# Roland_memser2308.net
KiCad netlist of a schematic drawn in EAGLE
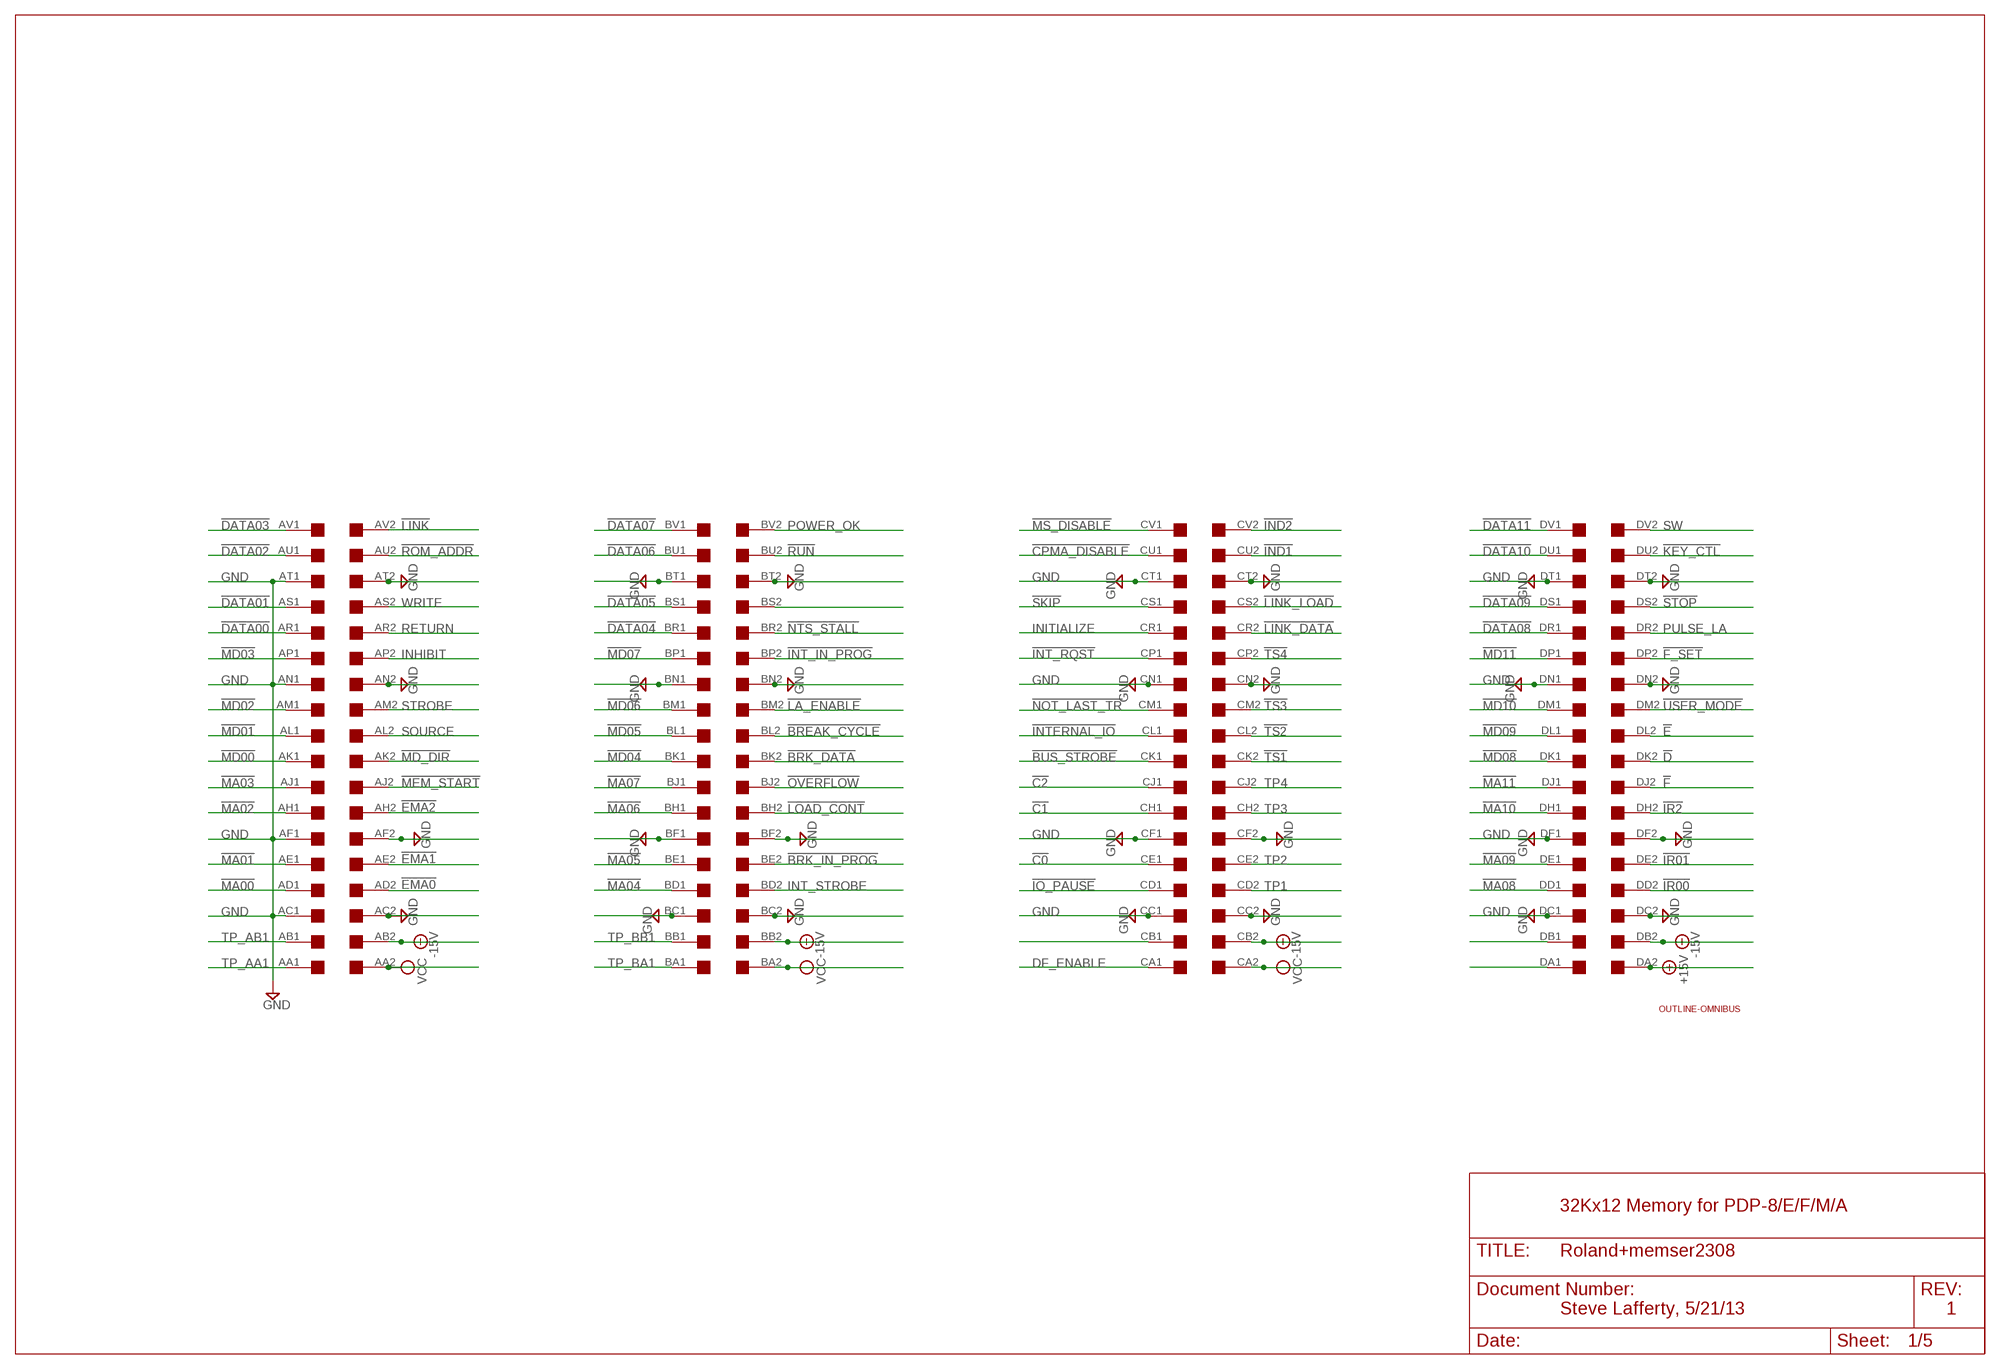
[diagram p0: schematic, sheet 1]
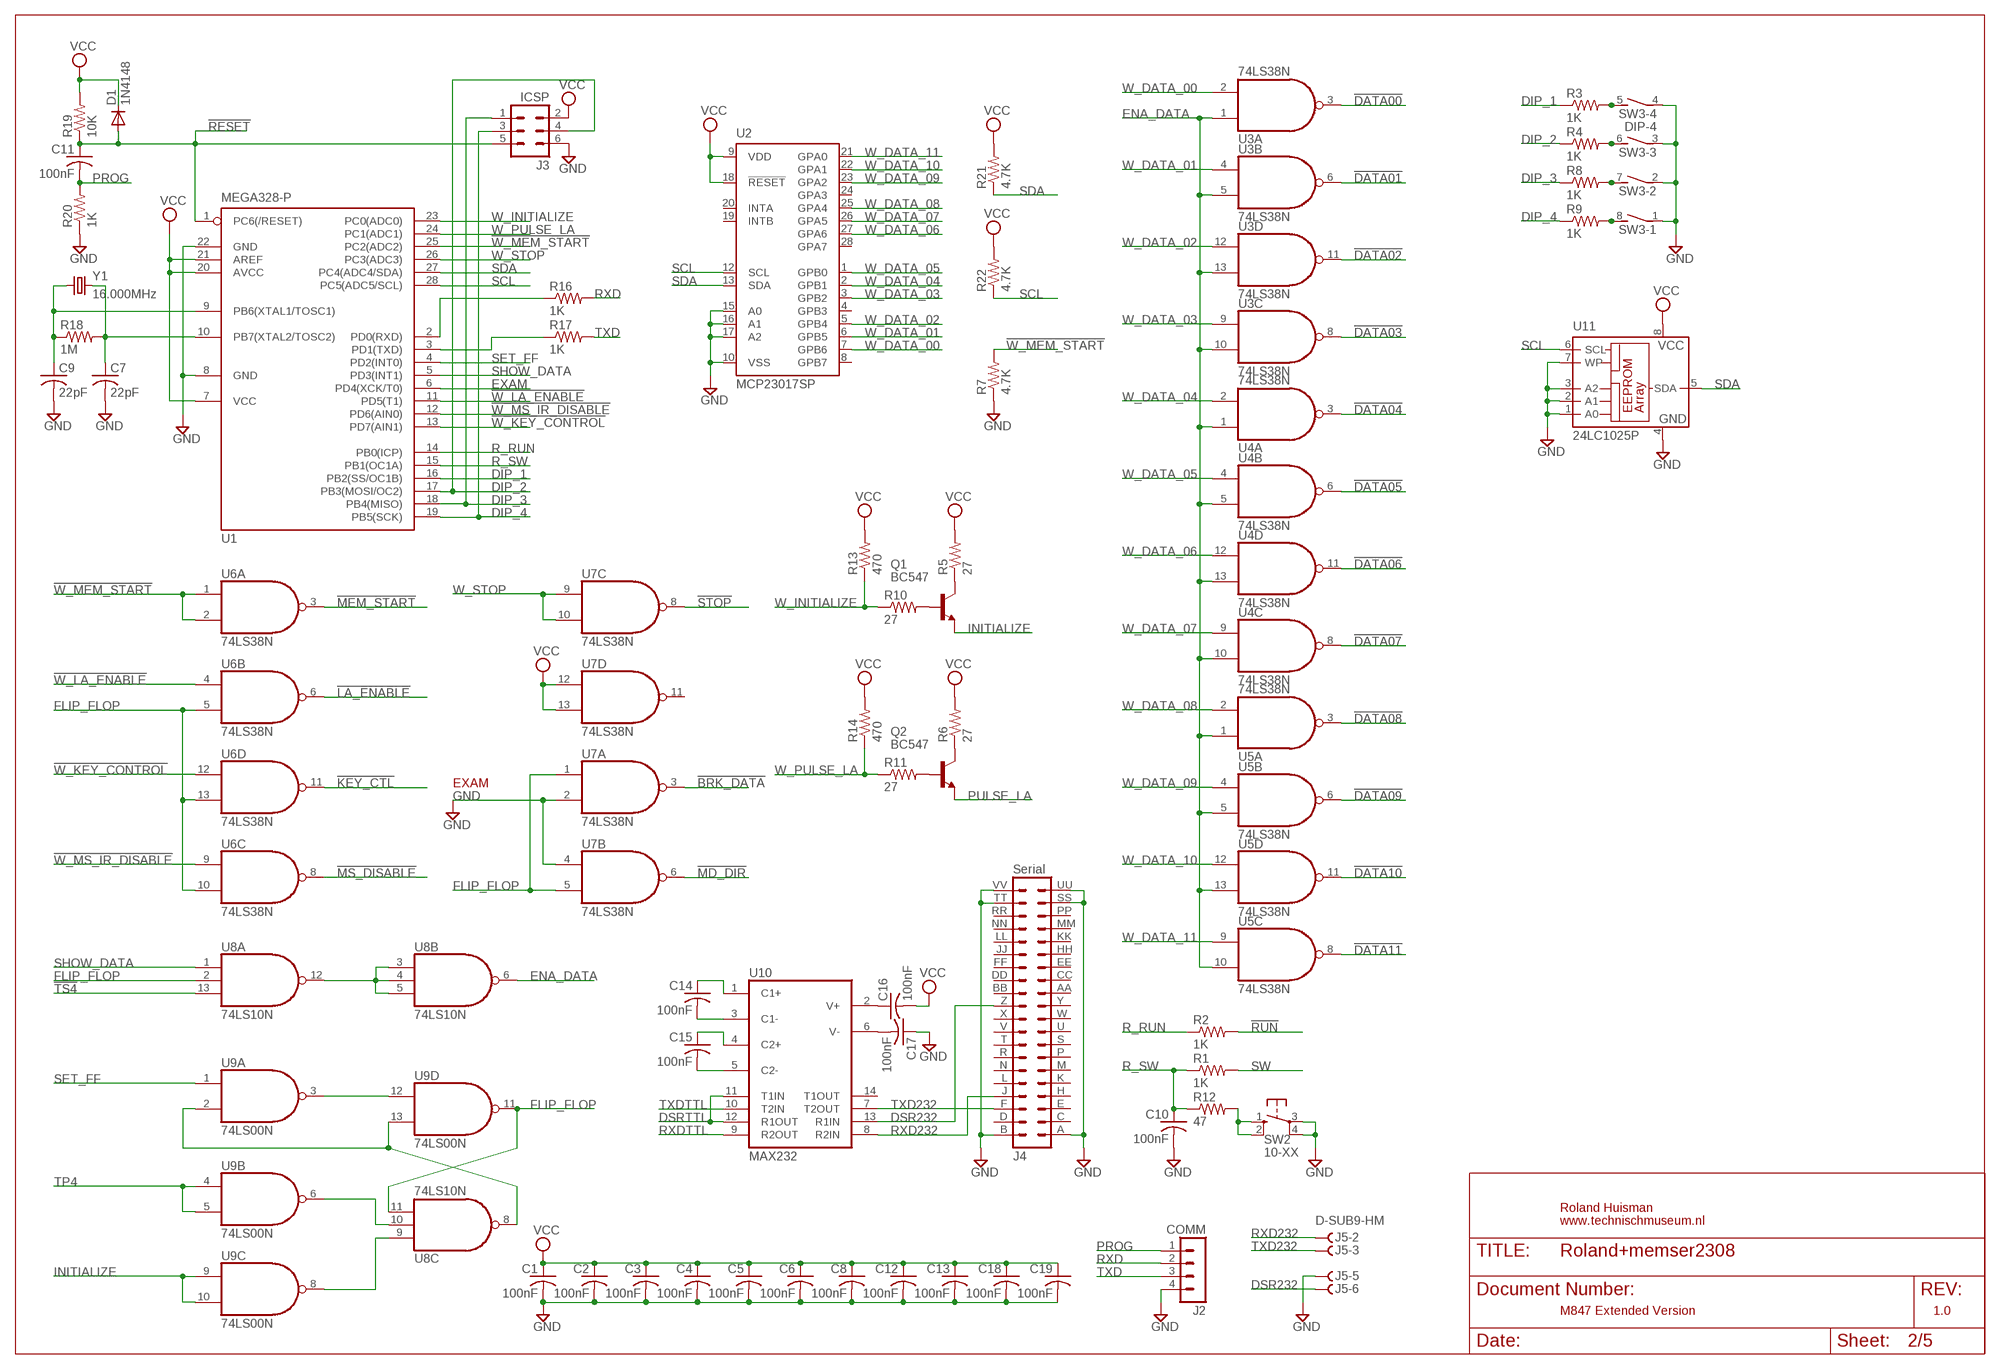
[diagram p1: schematic, sheet 2]
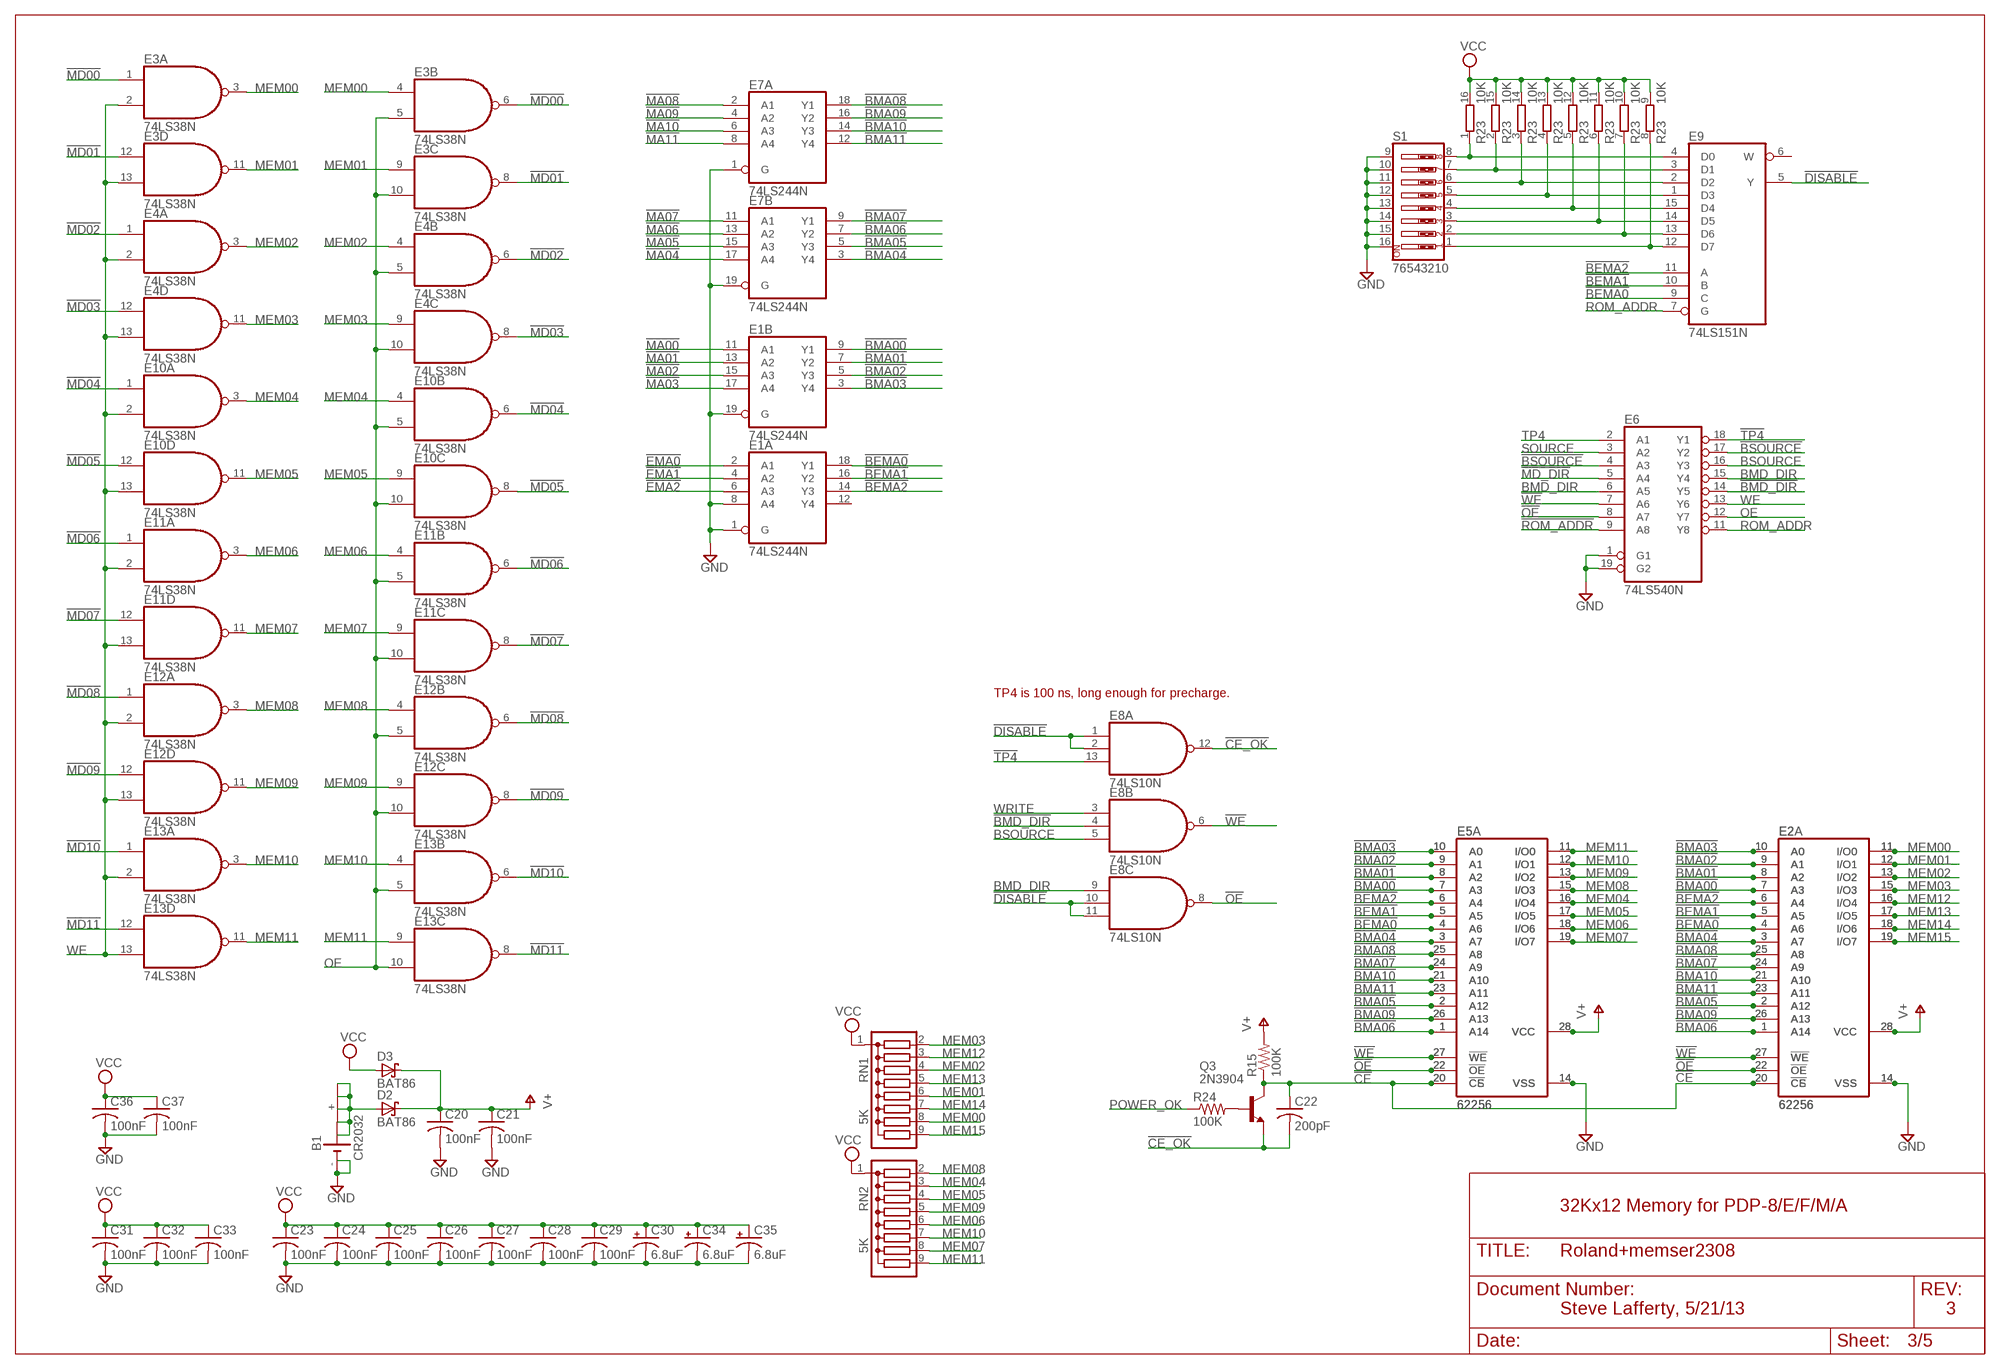
[diagram p2: schematic, sheet 3]
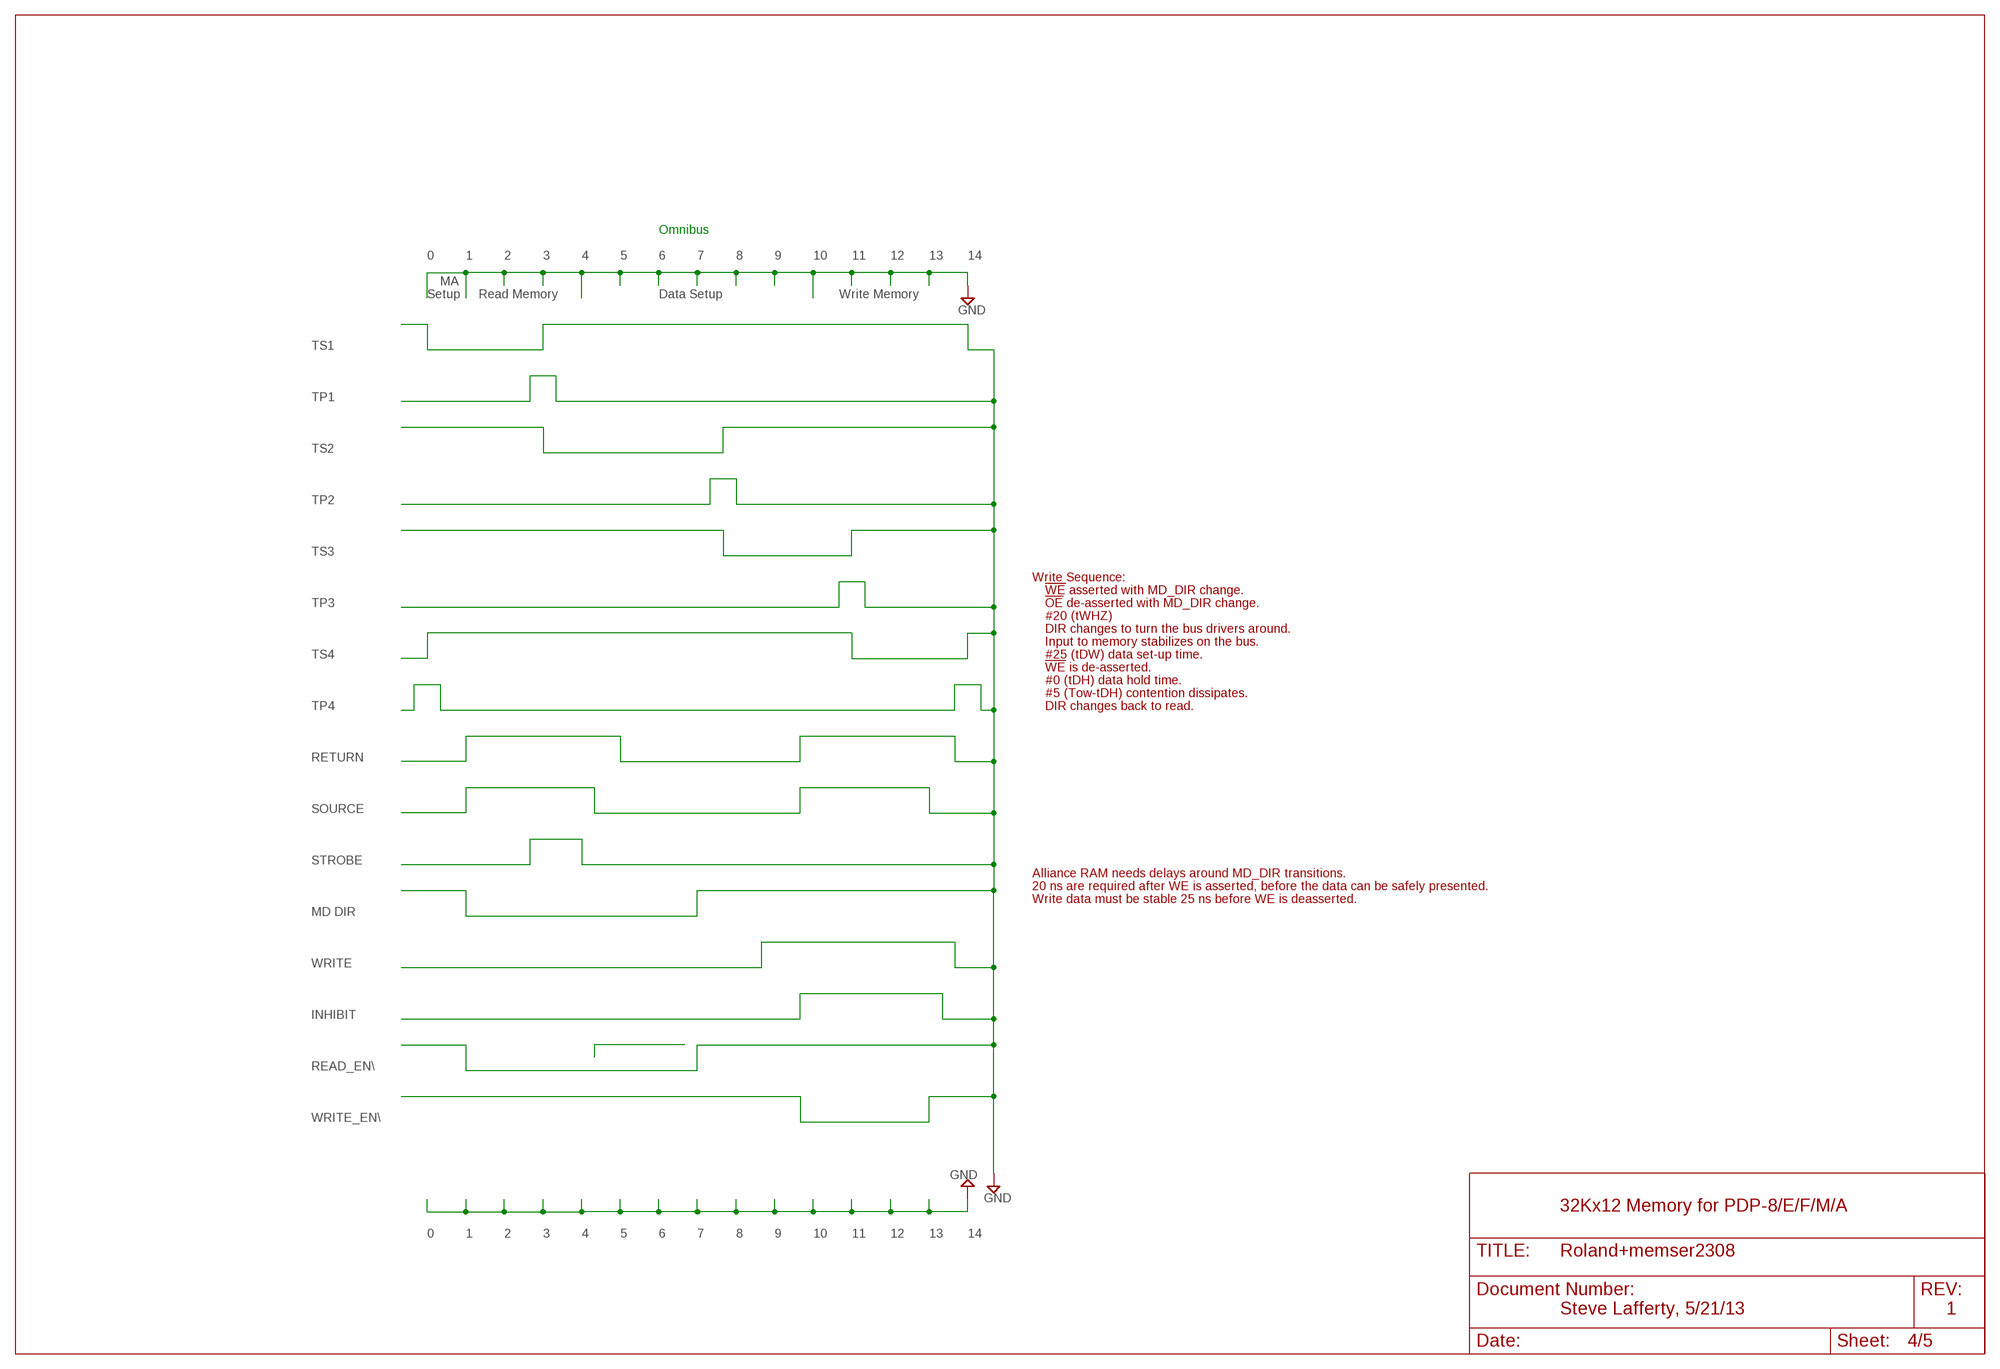
[diagram p3: schematic, sheet 4]
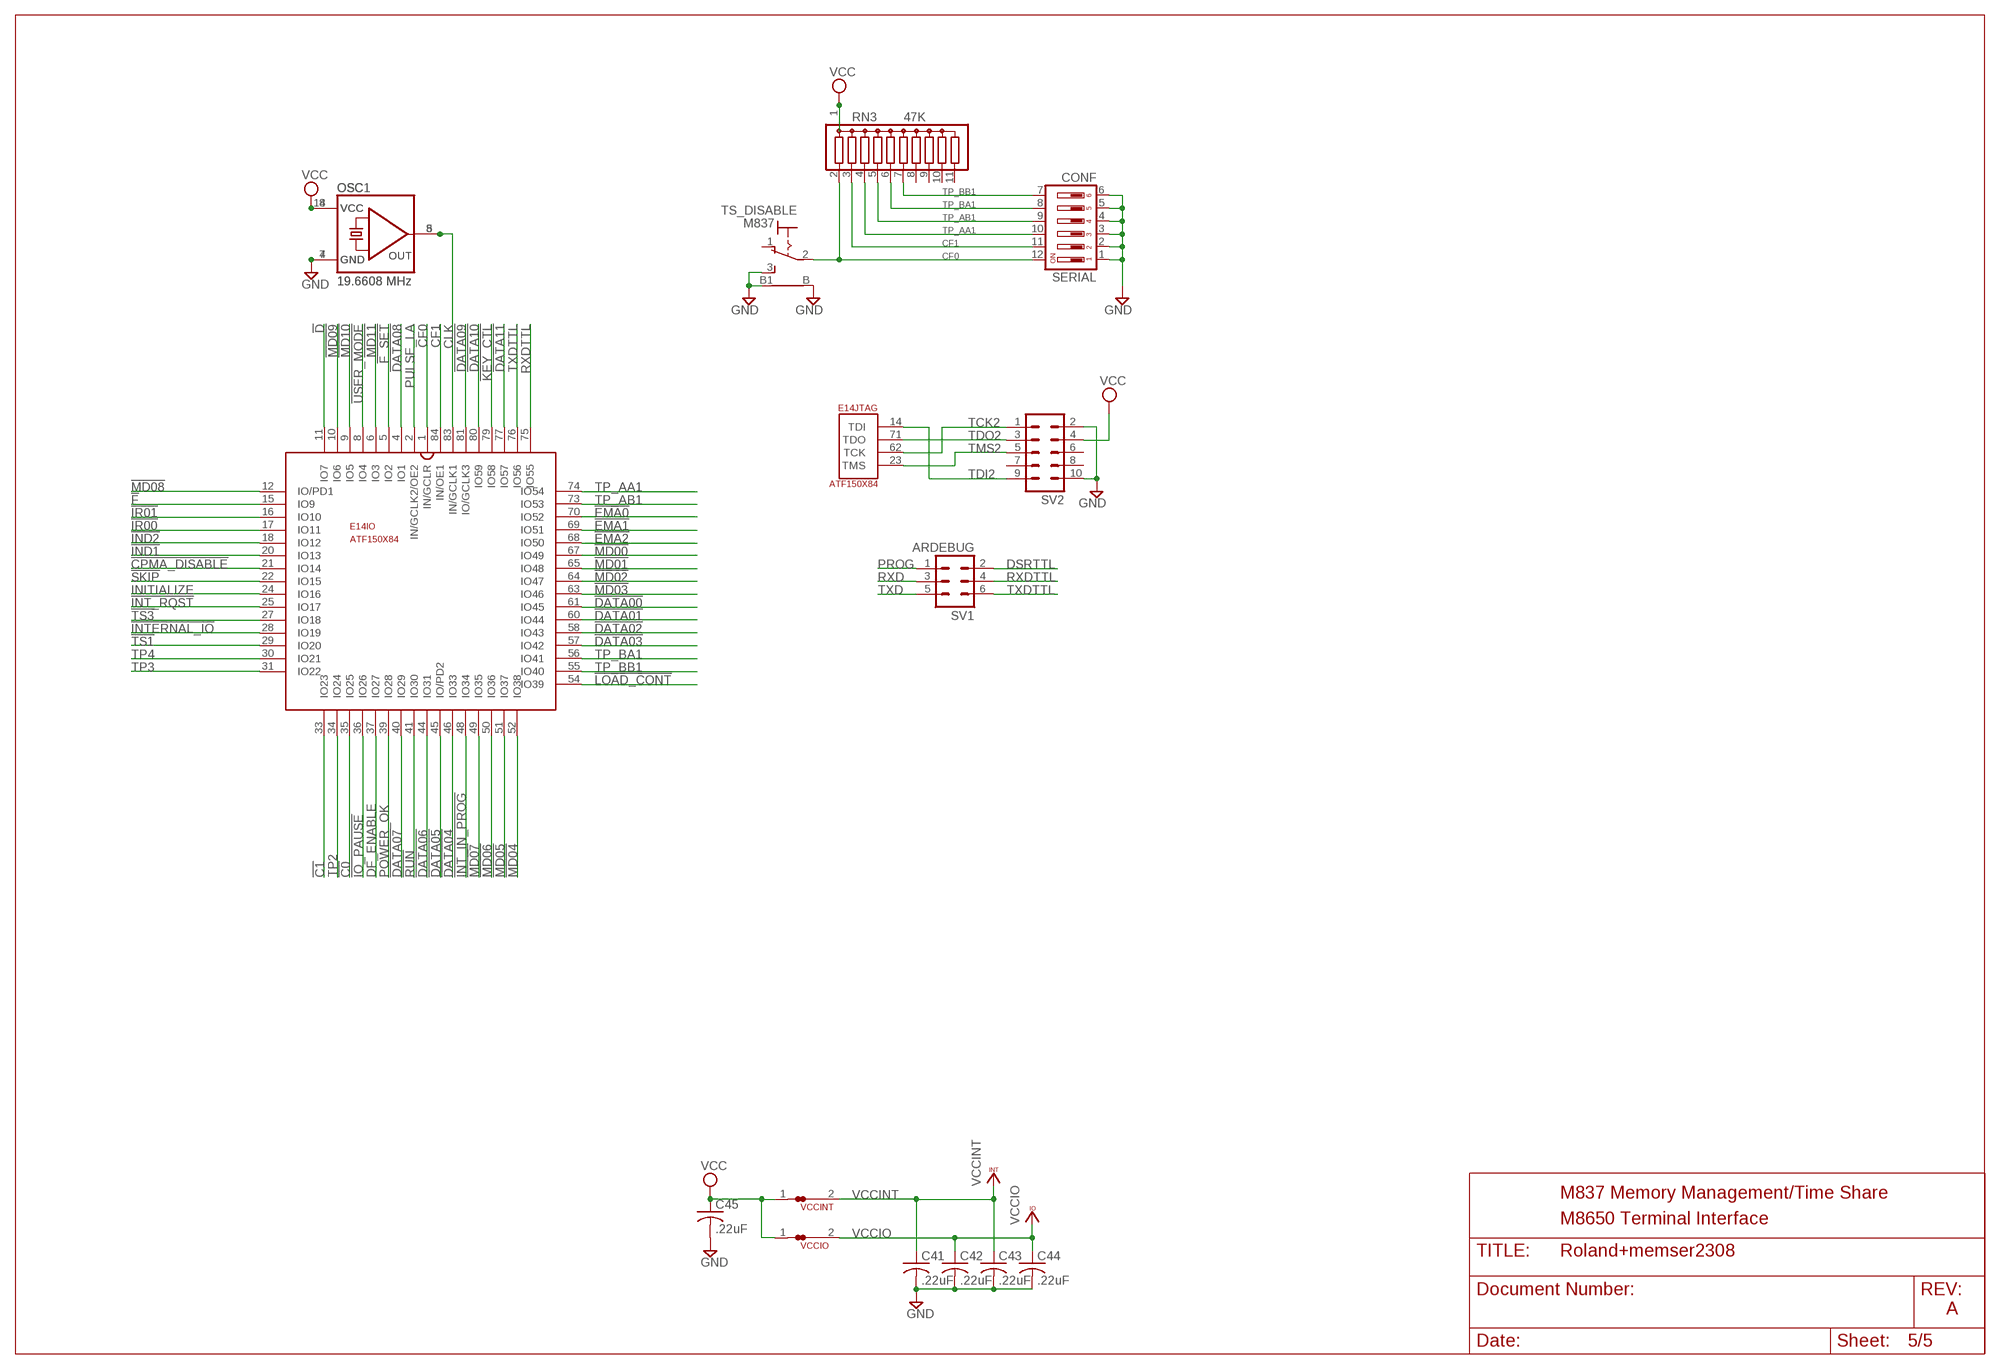
[diagram p4: schematic, sheet 5]

(export (version "E")
  (design (tool "Eeschema 10.0.6"))
  (components
    (comp (ref "C41")
      (value ".22uF")
      (footprint "eagle-import:C063-025X075")
      (libsource (lib "eagle-import") (part "C-US"))
    )
    (comp (ref "C42")
      (value ".22uF")
      (footprint "eagle-import:C063-025X075")
      (libsource (lib "eagle-import") (part "C-US"))
    )
    (comp (ref "C43")
      (value ".22uF")
      (footprint "eagle-import:C063-025X075")
      (libsource (lib "eagle-import") (part "C-US"))
    )
    (comp (ref "C44")
      (value ".22uF")
      (footprint "eagle-import:C063-025X075")
      (libsource (lib "eagle-import") (part "C-US"))
    )
    (comp (ref "C45")
      (value ".22uF")
      (footprint "eagle-import:C063-025X075")
      (libsource (lib "eagle-import") (part "C-US"))
    )
    (comp (ref "E14")
      (value "ATF150X84")
      (footprint "eagle-import:S84")
      (libsource (lib "eagle-import") (part "ATF150X84"))
    )
    (comp (ref "OSC")
      (value "19.6608 MHz")
      (footprint "eagle-import:DIL08S")
      (libsource (lib "eagle-import") (part "QG5460"))
    )
    (comp (ref "OSC1")
      (value "19.6608 MHz")
      (footprint "eagle-import:DIL14S")
      (libsource (lib "eagle-import") (part "QG5860"))
    )
    (comp (ref "RN3")
      (value "47K")
      (footprint "eagle-import:SIL11")
      (libsource (lib "eagle-import") (part "G10R"))
    )
    (comp (ref "SERIAL")
      (value "CONF")
      (footprint "eagle-import:DP-06")
      (fields (field (name "MPN") "MCDP06"))
      (libsource (lib "eagle-import") (part "DP06"))
    )
    (comp (ref "SV1")
      (value "ARDEBUG")
      (footprint "eagle-import:MA03-2")
      (libsource (lib "eagle-import") (part "MA03-2"))
    )
    (comp (ref "SV2")
      (value "ML10")
      (footprint "eagle-import:ML10")
      (libsource (lib "eagle-import") (part "ML10"))
    )
    (comp (ref "TS_DISABLE")
      (value "M837")
      (footprint "eagle-import:9070-1W")
      (libsource (lib "eagle-import") (part "9070-1W"))
    )
    (comp (ref "VCCINT")
      (value "JUMPER-NC1")
      (footprint "eagle-import:NC1")
      (libsource (lib "eagle-import") (part "JUMPER-NC1"))
    )
    (comp (ref "VCCIO")
      (value "JUMPER-NC1")
      (footprint "eagle-import:NC1")
      (libsource (lib "eagle-import") (part "JUMPER-NC1"))
    )
    (comp (ref "J1")
      (value "EDGE")
      (footprint "eagle-import:EDGE-CON8")
      (libsource (lib "eagle-import") (part "QUAD"))
    )
    (comp (ref "U$1")
      (value "OUTLINE-OMNIBUS")
      (footprint "eagle-import:OMNIBUS")
      (libsource (lib "eagle-import") (part "OUTLINE-OMNIBUS"))
    )
    (comp (ref "C1")
      (value "100nF")
      (footprint "eagle-import:C050-025X075")
      (libsource (lib "eagle-import") (part "C-US050-025X075"))
    )
    (comp (ref "C2")
      (value "100nF")
      (footprint "eagle-import:C050-025X075")
      (libsource (lib "eagle-import") (part "C-US050-025X075"))
    )
    (comp (ref "C3")
      (value "100nF")
      (footprint "eagle-import:C050-025X075")
      (libsource (lib "eagle-import") (part "C-US050-025X075"))
    )
    (comp (ref "C4")
      (value "100nF")
      (footprint "eagle-import:C050-025X075")
      (libsource (lib "eagle-import") (part "C-US050-025X075"))
    )
    (comp (ref "C5")
      (value "100nF")
      (footprint "eagle-import:C050-025X075")
      (libsource (lib "eagle-import") (part "C-US050-025X075"))
    )
    (comp (ref "C6")
      (value "100nF")
      (footprint "eagle-import:C050-025X075")
      (libsource (lib "eagle-import") (part "C-US050-025X075"))
    )
    (comp (ref "C7")
      (value "22pF")
      (footprint "eagle-import:C050-025X075")
      (libsource (lib "eagle-import") (part "C-US050-025X075"))
    )
    (comp (ref "C8")
      (value "100nF")
      (footprint "eagle-import:C050-025X075")
      (libsource (lib "eagle-import") (part "C-US050-025X075"))
    )
    (comp (ref "C9")
      (value "22pF")
      (footprint "eagle-import:C050-025X075")
      (libsource (lib "eagle-import") (part "C-US050-025X075"))
    )
    (comp (ref "C10")
      (value "100nF")
      (footprint "eagle-import:C050-025X075")
      (libsource (lib "eagle-import") (part "C-US050-025X075"))
    )
    (comp (ref "C11")
      (value "100nF")
      (footprint "eagle-import:C050-025X075")
      (libsource (lib "eagle-import") (part "C-US050-025X075"))
    )
    (comp (ref "C12")
      (value "100nF")
      (footprint "eagle-import:C050-025X075")
      (libsource (lib "eagle-import") (part "C-US050-025X075"))
    )
    (comp (ref "C13")
      (value "100nF")
      (footprint "eagle-import:C050-025X075")
      (libsource (lib "eagle-import") (part "C-US050-025X075"))
    )
    (comp (ref "C14")
      (value "100nF")
      (footprint "eagle-import:C050-025X075")
      (libsource (lib "eagle-import") (part "C-US050-025X075"))
    )
    (comp (ref "C15")
      (value "100nF")
      (footprint "eagle-import:C050-025X075")
      (libsource (lib "eagle-import") (part "C-US050-025X075"))
    )
    (comp (ref "C16")
      (value "100nF")
      (footprint "eagle-import:C050-025X075")
      (libsource (lib "eagle-import") (part "C-US050-025X075"))
    )
    (comp (ref "C17")
      (value "100nF")
      (footprint "eagle-import:C050-025X075")
      (libsource (lib "eagle-import") (part "C-US050-025X075"))
    )
    (comp (ref "C18")
      (value "100nF")
      (footprint "eagle-import:C050-025X075")
      (libsource (lib "eagle-import") (part "C-US050-025X075"))
    )
    (comp (ref "C19")
      (value "100nF")
      (footprint "eagle-import:C050-025X075")
      (libsource (lib "eagle-import") (part "C-US050-025X075"))
    )
    (comp (ref "D1")
      (value "1N4148")
      (footprint "eagle-import:DO35-10")
      (libsource (lib "eagle-import") (part "1N4148DO35-10"))
    )
    (comp (ref "J2")
      (value "COMM")
      (footprint "eagle-import:MA04-1")
      (libsource (lib "eagle-import") (part "MA04-1"))
    )
    (comp (ref "J3")
      (value "ICSP")
      (footprint "eagle-import:MA03-2")
      (libsource (lib "eagle-import") (part "MA03-2"))
    )
    (comp (ref "J4")
      (value "Serial")
      (footprint "eagle-import:DEC40PINH")
      (libsource (lib "eagle-import") (part "DEC40PINH"))
    )
    (comp (ref "J5")
      (value "D-SUB9-HM")
      (footprint "eagle-import:H5M09RA")
      (libsource (lib "eagle-import") (part "D-SUB9-H5M09RA"))
    )
    (comp (ref "Q1")
      (value "BC547")
      (footprint "eagle-import:TO5")
      (libsource (lib "eagle-import") (part "-NPN-TO5"))
    )
    (comp (ref "Q2")
      (value "BC547")
      (footprint "eagle-import:TO5")
      (libsource (lib "eagle-import") (part "-NPN-TO5"))
    )
    (comp (ref "R1")
      (value "1K")
      (footprint "eagle-import:0207_10")
      (libsource (lib "eagle-import") (part "R-US_0207/10"))
    )
    (comp (ref "R2")
      (value "1K")
      (footprint "eagle-import:0207_10")
      (libsource (lib "eagle-import") (part "R-US_0207/10"))
    )
    (comp (ref "R3")
      (value "1K")
      (footprint "eagle-import:0207_10")
      (libsource (lib "eagle-import") (part "R-US_0207/10"))
    )
    (comp (ref "R4")
      (value "1K")
      (footprint "eagle-import:0207_10")
      (libsource (lib "eagle-import") (part "R-US_0207/10"))
    )
    (comp (ref "R5")
      (value "27")
      (footprint "eagle-import:0207_10")
      (libsource (lib "eagle-import") (part "R-US_0207/10"))
    )
    (comp (ref "R6")
      (value "27")
      (footprint "eagle-import:0207_10")
      (libsource (lib "eagle-import") (part "R-US_0207/10"))
    )
    (comp (ref "R7")
      (value "4.7K")
      (footprint "eagle-import:0207_10")
      (libsource (lib "eagle-import") (part "R-US_0207/10"))
    )
    (comp (ref "R8")
      (value "1K")
      (footprint "eagle-import:0207_10")
      (libsource (lib "eagle-import") (part "R-US_0207/10"))
    )
    (comp (ref "R9")
      (value "1K")
      (footprint "eagle-import:0207_10")
      (libsource (lib "eagle-import") (part "R-US_0207/10"))
    )
    (comp (ref "R10")
      (value "27")
      (footprint "eagle-import:0207_10")
      (libsource (lib "eagle-import") (part "R-US_0207/10"))
    )
    (comp (ref "R11")
      (value "27")
      (footprint "eagle-import:0207_10")
      (libsource (lib "eagle-import") (part "R-US_0207/10"))
    )
    (comp (ref "R12")
      (value "47")
      (footprint "eagle-import:0207_10")
      (libsource (lib "eagle-import") (part "R-US_0207/10"))
    )
    (comp (ref "R13")
      (value "470")
      (footprint "eagle-import:0207_10")
      (libsource (lib "eagle-import") (part "R-US_0207/10"))
    )
    (comp (ref "R14")
      (value "470")
      (footprint "eagle-import:0207_10")
      (libsource (lib "eagle-import") (part "R-US_0207/10"))
    )
    (comp (ref "R16")
      (value "1K")
      (footprint "eagle-import:0207_10")
      (libsource (lib "eagle-import") (part "R-US_0207/10"))
    )
    (comp (ref "R17")
      (value "1K")
      (footprint "eagle-import:0207_10")
      (libsource (lib "eagle-import") (part "R-US_0207/10"))
    )
    (comp (ref "R18")
      (value "1M")
      (footprint "eagle-import:0207_10")
      (libsource (lib "eagle-import") (part "R-US_0207/10"))
    )
    (comp (ref "R19")
      (value "10K")
      (footprint "eagle-import:0207_10")
      (libsource (lib "eagle-import") (part "R-US_0207/10"))
    )
    (comp (ref "R20")
      (value "1K")
      (footprint "eagle-import:0207_10")
      (libsource (lib "eagle-import") (part "R-US_0207/10"))
    )
    (comp (ref "R21")
      (value "4.7K")
      (footprint "eagle-import:0207_10")
      (libsource (lib "eagle-import") (part "R-US_0207/10"))
    )
    (comp (ref "R22")
      (value "4.7K")
      (footprint "eagle-import:0207_10")
      (libsource (lib "eagle-import") (part "R-US_0207/10"))
    )
    (comp (ref "SW2")
      (value "10-XX")
      (footprint "eagle-import:B3F-10XX")
      (fields (field (name "MPN") "B3F-1000"))
      (libsource (lib "eagle-import") (part "10-XX"))
    )
    (comp (ref "SW3")
      (value "DIP-4")
      (footprint "eagle-import:DIP04S")
      (libsource (lib "eagle-import") (part "DIP04S"))
    )
    (comp (ref "U1")
      (value "MEGA328-P")
      (footprint "eagle-import:DIL28-3")
      (libsource (lib "eagle-import") (part "MEGA8-P"))
    )
    (comp (ref "U2")
      (value "MCP23017SP")
      (footprint "eagle-import:DIL28-3")
      (fields (field (name "MF") "MICROCHIP") (field (name "MPN") "MCP23017-E/SP"))
      (libsource (lib "eagle-import") (part "MCP23017SP"))
    )
    (comp (ref "U3")
      (value "74LS38N")
      (footprint "eagle-import:DIL14")
      (libsource (lib "eagle-import") (part "7438NLS"))
    )
    (comp (ref "U4")
      (value "74LS38N")
      (footprint "eagle-import:DIL14")
      (libsource (lib "eagle-import") (part "7438NLS"))
    )
    (comp (ref "U5")
      (value "74LS38N")
      (footprint "eagle-import:DIL14")
      (libsource (lib "eagle-import") (part "7438NLS"))
    )
    (comp (ref "U6")
      (value "74LS38N")
      (footprint "eagle-import:DIL14")
      (libsource (lib "eagle-import") (part "7438NLS"))
    )
    (comp (ref "U7")
      (value "74LS38N")
      (footprint "eagle-import:DIL14")
      (libsource (lib "eagle-import") (part "7438NLS"))
    )
    (comp (ref "U8")
      (value "74LS10N")
      (footprint "eagle-import:DIL14")
      (libsource (lib "eagle-import") (part "7410NLS"))
    )
    (comp (ref "U9")
      (value "74LS00N")
      (footprint "eagle-import:DIL14")
      (libsource (lib "eagle-import") (part "7400NLS"))
    )
    (comp (ref "U10")
      (value "MAX232")
      (footprint "eagle-import:DIL16")
      (fields (field (name "MF") "MAXIM") (field (name "MPN") "MAX232ACPE+"))
      (libsource (lib "eagle-import") (part "MAX232"))
    )
    (comp (ref "U11")
      (value "24LC1025P")
      (footprint "eagle-import:DIL8")
      (fields (field (name "MF") "MICROCHIP") (field (name "MPN") "24LC025-I/P"))
      (libsource (lib "eagle-import") (part "24PLC025"))
    )
    (comp (ref "Y1")
      (value "16.000MHz")
      (footprint "eagle-import:HC49U-H")
      (libsource (lib "eagle-import") (part "CRYSTALHC49U-H"))
    )
    (comp (ref "B1")
      (value "CR2032")
      (footprint "eagle-import:B2430UNI")
      (libsource (lib "eagle-import") (part "B2430UNI"))
    )
    (comp (ref "C20")
      (value "100nF")
      (footprint "eagle-import:C050-025X075")
      (libsource (lib "eagle-import") (part "C-US050-025X075"))
    )
    (comp (ref "C21")
      (value "100nF")
      (footprint "eagle-import:C050-025X075")
      (libsource (lib "eagle-import") (part "C-US050-025X075"))
    )
    (comp (ref "C22")
      (value "200pF")
      (footprint "eagle-import:C050-025X075")
      (libsource (lib "eagle-import") (part "C-US050-025X075"))
    )
    (comp (ref "C23")
      (value "100nF")
      (footprint "eagle-import:C050-025X075")
      (libsource (lib "eagle-import") (part "C-US050-025X075"))
    )
    (comp (ref "C24")
      (value "100nF")
      (footprint "eagle-import:C050-025X075")
      (libsource (lib "eagle-import") (part "C-US050-025X075"))
    )
    (comp (ref "C25")
      (value "100nF")
      (footprint "eagle-import:C050-025X075")
      (libsource (lib "eagle-import") (part "C-US050-025X075"))
    )
    (comp (ref "C26")
      (value "100nF")
      (footprint "eagle-import:C050-025X075")
      (libsource (lib "eagle-import") (part "C-US050-025X075"))
    )
    (comp (ref "C27")
      (value "100nF")
      (footprint "eagle-import:C050-025X075")
      (libsource (lib "eagle-import") (part "C-US050-025X075"))
    )
    (comp (ref "C28")
      (value "100nF")
      (footprint "eagle-import:C050-025X075")
      (libsource (lib "eagle-import") (part "C-US050-025X075"))
    )
    (comp (ref "C29")
      (value "100nF")
      (footprint "eagle-import:C050-025X075")
      (libsource (lib "eagle-import") (part "C-US050-025X075"))
    )
    (comp (ref "C30")
      (value "6.8uF")
      (footprint "eagle-import:E12-8")
      (libsource (lib "eagle-import") (part "CPOL-USE20-8AXIAL"))
    )
    (comp (ref "C31")
      (value "100nF")
      (footprint "eagle-import:C050-025X075")
      (libsource (lib "eagle-import") (part "C-US050-025X075"))
    )
    (comp (ref "C32")
      (value "100nF")
      (footprint "eagle-import:C050-025X075")
      (libsource (lib "eagle-import") (part "C-US050-025X075"))
    )
    (comp (ref "C33")
      (value "100nF")
      (footprint "eagle-import:C050-025X075")
      (libsource (lib "eagle-import") (part "C-US050-025X075"))
    )
    (comp (ref "C34")
      (value "6.8uF")
      (footprint "eagle-import:E12-8")
      (libsource (lib "eagle-import") (part "CPOL-USE20-8AXIAL"))
    )
    (comp (ref "C35")
      (value "6.8uF")
      (footprint "eagle-import:E12-8")
      (libsource (lib "eagle-import") (part "CPOL-USE20-8AXIAL"))
    )
    (comp (ref "C36")
      (value "100nF")
      (footprint "eagle-import:C050-025X075")
      (libsource (lib "eagle-import") (part "C-US050-025X075"))
    )
    (comp (ref "C37")
      (value "100nF")
      (footprint "eagle-import:C050-025X075")
      (libsource (lib "eagle-import") (part "C-US050-025X075"))
    )
    (comp (ref "D2")
      (value "BAT86")
      (footprint "eagle-import:DO35-10")
      (libsource (lib "eagle-import") (part "BAT19"))
    )
    (comp (ref "D3")
      (value "BAT86")
      (footprint "eagle-import:DO35-10")
      (libsource (lib "eagle-import") (part "BAT19"))
    )
    (comp (ref "E1")
      (value "74LS244N")
      (footprint "eagle-import:DIL20")
      (libsource (lib "eagle-import") (part "74244NLS"))
    )
    (comp (ref "E2")
      (value "62256")
      (footprint "eagle-import:DIL28-6")
      (libsource (lib "eagle-import") (part "58C256P"))
    )
    (comp (ref "E2A")
      (value "62256")
      (footprint "eagle-import:DIL28-3")
      (libsource (lib "eagle-import") (part "62832P"))
    )
    (comp (ref "E3")
      (value "74LS38N")
      (footprint "eagle-import:DIL14")
      (libsource (lib "eagle-import") (part "7438NLS"))
    )
    (comp (ref "E4")
      (value "74LS38N")
      (footprint "eagle-import:DIL14")
      (libsource (lib "eagle-import") (part "7438NLS"))
    )
    (comp (ref "E5")
      (value "62256")
      (footprint "eagle-import:DIL28-6")
      (libsource (lib "eagle-import") (part "58C256P"))
    )
    (comp (ref "E5A")
      (value "62256")
      (footprint "eagle-import:DIL28-3")
      (libsource (lib "eagle-import") (part "62832P"))
    )
    (comp (ref "E6")
      (value "74LS540N")
      (footprint "eagle-import:DIL20")
      (libsource (lib "eagle-import") (part "74540NLS"))
    )
    (comp (ref "E7")
      (value "74LS244N")
      (footprint "eagle-import:DIL20")
      (libsource (lib "eagle-import") (part "74244NLS"))
    )
    (comp (ref "E8")
      (value "74LS10N")
      (footprint "eagle-import:DIL14")
      (libsource (lib "eagle-import") (part "7410NLS"))
    )
    (comp (ref "E9")
      (value "74LS151N")
      (footprint "eagle-import:DIL16")
      (libsource (lib "eagle-import") (part "74151NLS"))
    )
    (comp (ref "E10")
      (value "74LS38N")
      (footprint "eagle-import:DIL14")
      (libsource (lib "eagle-import") (part "7438NLS"))
    )
    (comp (ref "E11")
      (value "74LS38N")
      (footprint "eagle-import:DIL14")
      (libsource (lib "eagle-import") (part "7438NLS"))
    )
    (comp (ref "E12")
      (value "74LS38N")
      (footprint "eagle-import:DIL14")
      (libsource (lib "eagle-import") (part "7438NLS"))
    )
    (comp (ref "E13")
      (value "74LS38N")
      (footprint "eagle-import:DIL14")
      (libsource (lib "eagle-import") (part "7438NLS"))
    )
    (comp (ref "Q3")
      (value "2N3904")
      (footprint "eagle-import:TO92")
      (libsource (lib "eagle-import") (part "2N3904"))
    )
    (comp (ref "R15")
      (value "100K")
      (footprint "eagle-import:0207_10")
      (libsource (lib "eagle-import") (part "R-US_0207/10"))
    )
    (comp (ref "R23")
      (value "10K")
      (footprint "eagle-import:DIL16")
      (libsource (lib "eagle-import") (part "8R-P"))
    )
    (comp (ref "R24")
      (value "100K")
      (footprint "eagle-import:0207_10")
      (libsource (lib "eagle-import") (part "R-US_0207/10"))
    )
    (comp (ref "RN1")
      (value "5K")
      (footprint "eagle-import:SIL9")
      (libsource (lib "eagle-import") (part "G08R"))
    )
    (comp (ref "RN2")
      (value "5K")
      (footprint "eagle-import:SIL9")
      (libsource (lib "eagle-import") (part "G08R"))
    )
    (comp (ref "S1")
      (value "76543210")
      (footprint "eagle-import:EDG-08")
      (libsource (lib "eagle-import") (part "SW_DIP-8"))
    )
  )
  (nets
    (net (code "1") (name "+15V") (class "Default")
      (node (ref "J1") (pin "DA2") (pinfunction "1_DA2") (pintype "bidirectional"))
    )
    (net (code "2") (name "-15V") (class "Default")
      (node (ref "J1") (pin "AB2") (pinfunction "1_AB2") (pintype "bidirectional"))
      (node (ref "J1") (pin "BB2") (pinfunction "1_BB2") (pintype "bidirectional"))
      (node (ref "J1") (pin "CB2") (pinfunction "1_CB2") (pintype "bidirectional"))
      (node (ref "J1") (pin "DB2") (pinfunction "1_DB2") (pintype "bidirectional"))
    )
    (net (code "3") (name "BMD_DIR") (class "Default")
      (node (ref "E6") (pin "15") (pinfunction "Y4_15") (pintype "tri_state"))
      (node (ref "E6") (pin "6") (pinfunction "A5_6") (pintype "input"))
      (node (ref "E8") (pin "9") (pinfunction "I0_9") (pintype "input"))
    )
    (net (code "4") (name "BSOURCE") (class "Default")
      (node (ref "E6") (pin "16") (pinfunction "Y3_16") (pintype "tri_state"))
      (node (ref "E8") (pin "5") (pinfunction "I2_5") (pintype "input"))
    )
    (net (code "5") (name "CF0") (class "Default")
      (node (ref "E14") (pin "1") (pinfunction "IN/GCLR_1") (pintype "input"))
      (node (ref "RN3") (pin "2") (pinfunction "2_2") (pintype "passive"))
      (node (ref "SERIAL") (pin "12") (pinfunction "12_12") (pintype "passive"))
      (node (ref "TS_DISABLE") (pin "2") (pinfunction "P_2") (pintype "passive"))
    )
    (net (code "6") (name "CF1") (class "Default")
      (node (ref "E14") (pin "84") (pinfunction "IN/OE1_84") (pintype "input"))
      (node (ref "RN3") (pin "3") (pinfunction "3_3") (pintype "passive"))
      (node (ref "SERIAL") (pin "11") (pinfunction "11_11") (pintype "passive"))
    )
    (net (code "7") (name "CLK") (class "Default")
      (node (ref "E14") (pin "83") (pinfunction "IN/GCLK1_83") (pintype "input"))
      (node (ref "OSC") (pin "5") (pinfunction "OUT_5") (pintype "output"))
      (node (ref "OSC1") (pin "8") (pinfunction "OUT_8") (pintype "output"))
    )
    (net (code "8") (name "DF_ENABLE") (class "Default")
      (node (ref "E14") (pin "37") (pinfunction "IO27_37") (pintype "bidirectional"))
      (node (ref "J1") (pin "CA1") (pinfunction "1_CA1") (pintype "bidirectional"))
    )
    (net (code "9") (name "DIP_1") (class "Default")
      (node (ref "R3") (pin "1") (pinfunction "1_1") (pintype "passive"))
      (node (ref "U1") (pin "16") (pinfunction "PB2(SS/OC1B)_16") (pintype "bidirectional"))
    )
    (net (code "10") (name "DIP_2") (class "Default")
      (node (ref "J3") (pin "4") (pinfunction "4_4") (pintype "passive"))
      (node (ref "R4") (pin "1") (pinfunction "1_1") (pintype "passive"))
      (node (ref "U1") (pin "17") (pinfunction "PB3(MOSI/OC2)_17") (pintype "bidirectional"))
    )
    (net (code "11") (name "DIP_3") (class "Default")
      (node (ref "J3") (pin "1") (pinfunction "1_1") (pintype "passive"))
      (node (ref "R8") (pin "1") (pinfunction "1_1") (pintype "passive"))
      (node (ref "U1") (pin "18") (pinfunction "PB4(MISO)_18") (pintype "bidirectional"))
    )
    (net (code "12") (name "DIP_4") (class "Default")
      (node (ref "J3") (pin "3") (pinfunction "3_3") (pintype "passive"))
      (node (ref "R9") (pin "1") (pinfunction "1_1") (pintype "passive"))
      (node (ref "U1") (pin "19") (pinfunction "PB5(SCK)_19") (pintype "bidirectional"))
    )
    (net (code "13") (name "DSR232") (class "Default")
      (node (ref "J4") (pin "Z") (pinfunction "22_Z") (pintype "bidirectional"))
      (node (ref "J5") (pin "6") (pinfunction "F_6") (pintype "passive"))
      (node (ref "U10") (pin "13") (pinfunction "R1IN_13") (pintype "input"))
    )
    (net (code "14") (name "DSRTTL") (class "Default")
      (node (ref "SV1") (pin "2") (pinfunction "2_2") (pintype "passive"))
      (node (ref "U10") (pin "11") (pinfunction "T1IN_11") (pintype "input"))
      (node (ref "U10") (pin "12") (pinfunction "R1OUT_12") (pintype "output"))
    )
    (net (code "15") (name "ENA_DATA") (class "Default")
      (node (ref "U3") (pin "1") (pinfunction "I0_1") (pintype "input"))
      (node (ref "U3") (pin "10") (pinfunction "I1_10") (pintype "input"))
      (node (ref "U3") (pin "13") (pinfunction "I1_13") (pintype "input"))
      (node (ref "U3") (pin "5") (pinfunction "I1_5") (pintype "input"))
      (node (ref "U4") (pin "1") (pinfunction "I0_1") (pintype "input"))
      (node (ref "U4") (pin "10") (pinfunction "I1_10") (pintype "input"))
      (node (ref "U4") (pin "13") (pinfunction "I1_13") (pintype "input"))
      (node (ref "U4") (pin "5") (pinfunction "I1_5") (pintype "input"))
      (node (ref "U5") (pin "1") (pinfunction "I0_1") (pintype "input"))
      (node (ref "U5") (pin "10") (pinfunction "I1_10") (pintype "input"))
      (node (ref "U5") (pin "13") (pinfunction "I1_13") (pintype "input"))
      (node (ref "U5") (pin "5") (pinfunction "I1_5") (pintype "input"))
      (node (ref "U8") (pin "6") (pinfunction "O_6") (pintype "output"))
    )
    (net (code "16") (name "EXAM") (class "Default")
      (node (ref "U1") (pin "6") (pinfunction "PD4(XCK/T0)_6") (pintype "bidirectional"))
    )
    (net (code "17") (name "FLIP_FLOP") (class "Default")
      (node (ref "U6") (pin "10") (pinfunction "I1_10") (pintype "input"))
      (node (ref "U6") (pin "13") (pinfunction "I1_13") (pintype "input"))
      (node (ref "U6") (pin "5") (pinfunction "I1_5") (pintype "input"))
      (node (ref "U7") (pin "1") (pinfunction "I0_1") (pintype "input"))
      (node (ref "U7") (pin "5") (pinfunction "I1_5") (pintype "input"))
      (node (ref "U8") (pin "11") (pinfunction "I2_11") (pintype "input"))
      (node (ref "U8") (pin "2") (pinfunction "I1_2") (pintype "input"))
      (node (ref "U9") (pin "11") (pinfunction "O_11") (pintype "output"))
    )
    (net (code "18") (name "GND") (class "Default")
      (node (ref "B1") (pin "-") (pinfunction "-_-") (pintype "passive"))
      (node (ref "B1") (pin "-@1") (pinfunction "-_-@1") (pintype "passive"))
      (node (ref "C1") (pin "2") (pinfunction "2_2") (pintype "passive"))
      (node (ref "C10") (pin "2") (pinfunction "2_2") (pintype "passive"))
      (node (ref "C12") (pin "2") (pinfunction "2_2") (pintype "passive"))
      (node (ref "C13") (pin "2") (pinfunction "2_2") (pintype "passive"))
      (node (ref "C17") (pin "1") (pinfunction "1_1") (pintype "passive"))
      (node (ref "C18") (pin "2") (pinfunction "2_2") (pintype "passive"))
      (node (ref "C19") (pin "2") (pinfunction "2_2") (pintype "passive"))
      (node (ref "C2") (pin "2") (pinfunction "2_2") (pintype "passive"))
      (node (ref "C20") (pin "2") (pinfunction "2_2") (pintype "passive"))
      (node (ref "C21") (pin "2") (pinfunction "2_2") (pintype "passive"))
      (node (ref "C23") (pin "2") (pinfunction "2_2") (pintype "passive"))
      (node (ref "C24") (pin "2") (pinfunction "2_2") (pintype "passive"))
      (node (ref "C25") (pin "2") (pinfunction "2_2") (pintype "passive"))
      (node (ref "C26") (pin "2") (pinfunction "2_2") (pintype "passive"))
      (node (ref "C27") (pin "2") (pinfunction "2_2") (pintype "passive"))
      (node (ref "C28") (pin "2") (pinfunction "2_2") (pintype "passive"))
      (node (ref "C29") (pin "2") (pinfunction "2_2") (pintype "passive"))
      (node (ref "C3") (pin "2") (pinfunction "2_2") (pintype "passive"))
      (node (ref "C30") (pin "-") (pinfunction "-_-") (pintype "passive"))
      (node (ref "C31") (pin "2") (pinfunction "2_2") (pintype "passive"))
      (node (ref "C32") (pin "2") (pinfunction "2_2") (pintype "passive"))
      (node (ref "C33") (pin "2") (pinfunction "2_2") (pintype "passive"))
      (node (ref "C34") (pin "-") (pinfunction "-_-") (pintype "passive"))
      (node (ref "C35") (pin "-") (pinfunction "-_-") (pintype "passive"))
      (node (ref "C36") (pin "2") (pinfunction "2_2") (pintype "passive"))
      (node (ref "C37") (pin "2") (pinfunction "2_2") (pintype "passive"))
      (node (ref "C4") (pin "2") (pinfunction "2_2") (pintype "passive"))
      (node (ref "C41") (pin "2") (pinfunction "2_2") (pintype "passive"))
      (node (ref "C42") (pin "2") (pinfunction "2_2") (pintype "passive"))
      (node (ref "C43") (pin "2") (pinfunction "2_2") (pintype "passive"))
      (node (ref "C44") (pin "2") (pinfunction "2_2") (pintype "passive"))
      (node (ref "C45") (pin "2") (pinfunction "2_2") (pintype "passive"))
      (node (ref "C5") (pin "2") (pinfunction "2_2") (pintype "passive"))
      (node (ref "C6") (pin "2") (pinfunction "2_2") (pintype "passive"))
      (node (ref "C7") (pin "2") (pinfunction "2_2") (pintype "passive"))
      (node (ref "C8") (pin "2") (pinfunction "2_2") (pintype "passive"))
      (node (ref "C9") (pin "2") (pinfunction "2_2") (pintype "passive"))
      (node (ref "E1") (pin "1") (pinfunction "G_1") (pintype "input"))
      (node (ref "E1") (pin "19") (pinfunction "G_19") (pintype "input"))
      (node (ref "E1") (pin "8") (pinfunction "A4_8") (pintype "input"))
      (node (ref "E2") (pin "14") (pinfunction "VSS_14") (pintype "power_in"))
      (node (ref "E2A") (pin "14") (pinfunction "VSS_14") (pintype "power_in"))
      (node (ref "E5") (pin "14") (pinfunction "VSS_14") (pintype "power_in"))
      (node (ref "E5A") (pin "14") (pinfunction "VSS_14") (pintype "power_in"))
      (node (ref "E6") (pin "1") (pinfunction "G1_1") (pintype "input"))
      (node (ref "E6") (pin "19") (pinfunction "G2_19") (pintype "input"))
      (node (ref "E7") (pin "1") (pinfunction "G_1") (pintype "input"))
      (node (ref "E7") (pin "19") (pinfunction "G_19") (pintype "input"))
      (node (ref "J1") (pin "AC1") (pinfunction "1_AC1") (pintype "bidirectional"))
      (node (ref "J1") (pin "AC2") (pinfunction "1_AC2") (pintype "bidirectional"))
      (node (ref "J1") (pin "AF1") (pinfunction "1_AF1") (pintype "bidirectional"))
      (node (ref "J1") (pin "AF2") (pinfunction "1_AF2") (pintype "bidirectional"))
      (node (ref "J1") (pin "AN1") (pinfunction "1_AN1") (pintype "bidirectional"))
      (node (ref "J1") (pin "AN2") (pinfunction "1_AN2") (pintype "bidirectional"))
      (node (ref "J1") (pin "AT1") (pinfunction "1_AT1") (pintype "bidirectional"))
      (node (ref "J1") (pin "AT2") (pinfunction "1_AT2") (pintype "bidirectional"))
      (node (ref "J1") (pin "BC1") (pinfunction "1_BC1") (pintype "bidirectional"))
      (node (ref "J1") (pin "BC2") (pinfunction "1_BC2") (pintype "bidirectional"))
      (node (ref "J1") (pin "BF1") (pinfunction "1_BF1") (pintype "bidirectional"))
      (node (ref "J1") (pin "BF2") (pinfunction "1_BF2") (pintype "bidirectional"))
      (node (ref "J1") (pin "BN1") (pinfunction "1_BN1") (pintype "bidirectional"))
      (node (ref "J1") (pin "BN2") (pinfunction "1_BN2") (pintype "bidirectional"))
      (node (ref "J1") (pin "BT1") (pinfunction "1_BT1") (pintype "bidirectional"))
      (node (ref "J1") (pin "BT2") (pinfunction "1_BT2") (pintype "bidirectional"))
      (node (ref "J1") (pin "CC1") (pinfunction "1_CC1") (pintype "bidirectional"))
      (node (ref "J1") (pin "CC2") (pinfunction "1_CC2") (pintype "bidirectional"))
      (node (ref "J1") (pin "CF1") (pinfunction "1_CF1") (pintype "bidirectional"))
      (node (ref "J1") (pin "CF2") (pinfunction "1_CF2") (pintype "bidirectional"))
      (node (ref "J1") (pin "CN1") (pinfunction "1_CN1") (pintype "bidirectional"))
      (node (ref "J1") (pin "CN2") (pinfunction "1_CN2") (pintype "bidirectional"))
      (node (ref "J1") (pin "CT1") (pinfunction "1_CT1") (pintype "bidirectional"))
      (node (ref "J1") (pin "CT2") (pinfunction "1_CT2") (pintype "bidirectional"))
      (node (ref "J1") (pin "DC1") (pinfunction "1_DC1") (pintype "bidirectional"))
      (node (ref "J1") (pin "DC2") (pinfunction "1_DC2") (pintype "bidirectional"))
      (node (ref "J1") (pin "DF1") (pinfunction "1_DF1") (pintype "bidirectional"))
      (node (ref "J1") (pin "DF2") (pinfunction "1_DF2") (pintype "bidirectional"))
      (node (ref "J1") (pin "DN1") (pinfunction "1_DN1") (pintype "bidirectional"))
      (node (ref "J1") (pin "DN2") (pinfunction "1_DN2") (pintype "bidirectional"))
      (node (ref "J1") (pin "DT1") (pinfunction "1_DT1") (pintype "bidirectional"))
      (node (ref "J1") (pin "DT2") (pinfunction "1_DT2") (pintype "bidirectional"))
      (node (ref "J2") (pin "4") (pinfunction "4_4") (pintype "passive"))
      (node (ref "J3") (pin "6") (pinfunction "6_6") (pintype "passive"))
      (node (ref "J4") (pin "A") (pinfunction "1_A") (pintype "bidirectional"))
      (node (ref "J4") (pin "B") (pinfunction "2_B") (pintype "bidirectional"))
      (node (ref "J4") (pin "SS") (pinfunction "37_SS") (pintype "bidirectional"))
      (node (ref "J4") (pin "TT") (pinfunction "38_TT") (pintype "bidirectional"))
      (node (ref "J4") (pin "UU") (pinfunction "39_UU") (pintype "bidirectional"))
      (node (ref "J4") (pin "VV") (pinfunction "40_VV") (pintype "bidirectional"))
      (node (ref "J5") (pin "5") (pinfunction "F_5") (pintype "passive"))
      (node (ref "OSC") (pin "4") (pinfunction "GND_4") (pintype "power_in"))
      (node (ref "OSC1") (pin "7") (pinfunction "GND_7") (pintype "power_in"))
      (node (ref "R20") (pin "1") (pinfunction "1_1") (pintype "passive"))
      (node (ref "R7") (pin "1") (pinfunction "1_1") (pintype "passive"))
      (node (ref "S1") (pin "10") (pinfunction "10_10") (pintype "passive"))
      (node (ref "S1") (pin "11") (pinfunction "11_11") (pintype "passive"))
      (node (ref "S1") (pin "12") (pinfunction "12_12") (pintype "passive"))
      (node (ref "S1") (pin "13") (pinfunction "13_13") (pintype "passive"))
      (node (ref "S1") (pin "14") (pinfunction "14_14") (pintype "passive"))
      (node (ref "S1") (pin "15") (pinfunction "15_15") (pintype "passive"))
      (node (ref "S1") (pin "16") (pinfunction "16_16") (pintype "passive"))
      (node (ref "S1") (pin "9") (pinfunction "9_9") (pintype "passive"))
      (node (ref "SERIAL") (pin "1") (pinfunction "1_1") (pintype "passive"))
      (node (ref "SERIAL") (pin "2") (pinfunction "2_2") (pintype "passive"))
      (node (ref "SERIAL") (pin "3") (pinfunction "3_3") (pintype "passive"))
      (node (ref "SERIAL") (pin "4") (pinfunction "4_4") (pintype "passive"))
      (node (ref "SERIAL") (pin "5") (pinfunction "5_5") (pintype "passive"))
      (node (ref "SERIAL") (pin "6") (pinfunction "6_6") (pintype "passive"))
      (node (ref "SV2") (pin "10") (pinfunction "10_10") (pintype "passive"))
      (node (ref "SV2") (pin "2") (pinfunction "2_2") (pintype "passive"))
      (node (ref "SW2") (pin "3") (pinfunction "P_3") (pintype "passive"))
      (node (ref "SW2") (pin "4") (pinfunction "P1_4") (pintype "passive"))
      (node (ref "SW3") (pin "1") (pinfunction "1_1") (pintype "passive"))
      (node (ref "SW3") (pin "2") (pinfunction "1_2") (pintype "passive"))
      (node (ref "SW3") (pin "3") (pinfunction "1_3") (pintype "passive"))
      (node (ref "SW3") (pin "4") (pinfunction "1_4") (pintype "passive"))
      (node (ref "TS_DISABLE") (pin "3") (pinfunction "S_3") (pintype "passive"))
      (node (ref "TS_DISABLE") (pin "B") (pinfunction "B_B") (pintype "passive"))
      (node (ref "TS_DISABLE") (pin "B1") (pinfunction "B1_B1") (pintype "passive"))
      (node (ref "U1") (pin "22") (pinfunction "GND_22") (pintype "power_in"))
      (node (ref "U1") (pin "8") (pinfunction "GND_8") (pintype "power_in"))
      (node (ref "U11") (pin "1") (pinfunction "A0_1") (pintype "input"))
      (node (ref "U11") (pin "2") (pinfunction "A1_2") (pintype "input"))
      (node (ref "U11") (pin "3") (pinfunction "A2_3") (pintype "input"))
      (node (ref "U11") (pin "4") (pinfunction "GND_4") (pintype "power_in"))
      (node (ref "U11") (pin "7") (pinfunction "WP_7") (pintype "input"))
      (node (ref "U2") (pin "10") (pinfunction "VSS_10") (pintype "power_in"))
      (node (ref "U2") (pin "15") (pinfunction "A0_15") (pintype "input"))
      (node (ref "U2") (pin "16") (pinfunction "A1_16") (pintype "input"))
      (node (ref "U2") (pin "17") (pinfunction "A2_17") (pintype "input"))
      (node (ref "U7") (pin "2") (pinfunction "I1_2") (pintype "input"))
      (node (ref "U7") (pin "4") (pinfunction "I0_4") (pintype "input"))
    )
    (net (code "19") (name "INHIBIT") (class "Default")
      (node (ref "J1") (pin "AP2") (pinfunction "1_AP2") (pintype "bidirectional"))
    )
    (net (code "20") (name "INITIALIZE") (class "Default")
      (node (ref "E14") (pin "24") (pinfunction "IO16_24") (pintype "bidirectional"))
      (node (ref "J1") (pin "CR1") (pinfunction "1_CR1") (pintype "bidirectional"))
      (node (ref "Q1") (pin "1") (pinfunction "E_1") (pintype "passive"))
      (node (ref "U9") (pin "10") (pinfunction "I1_10") (pintype "input"))
      (node (ref "U9") (pin "9") (pinfunction "I0_9") (pintype "input"))
    )
    (net (code "21") (name "INT_STROBE") (class "Default")
      (node (ref "J1") (pin "BD2") (pinfunction "1_BD2") (pintype "bidirectional"))
    )
    (net (code "22") (name "MEM00") (class "Default")
      (node (ref "E2") (pin "11") (pinfunction "I/O0_11") (pintype "tri_state"))
      (node (ref "E2A") (pin "11") (pinfunction "I/O0_11") (pintype "bidirectional"))
      (node (ref "E3") (pin "3") (pinfunction "O_3") (pintype "open_collector"))
      (node (ref "E3") (pin "4") (pinfunction "I0_4") (pintype "input"))
      (node (ref "RN1") (pin "8") (pinfunction "8_8") (pintype "passive"))
    )
    (net (code "23") (name "MEM01") (class "Default")
      (node (ref "E2") (pin "12") (pinfunction "I/O1_12") (pintype "tri_state"))
      (node (ref "E2A") (pin "12") (pinfunction "I/O1_12") (pintype "bidirectional"))
      (node (ref "E3") (pin "11") (pinfunction "O_11") (pintype "open_collector"))
      (node (ref "E3") (pin "9") (pinfunction "I0_9") (pintype "input"))
      (node (ref "RN1") (pin "6") (pinfunction "6_6") (pintype "passive"))
    )
    (net (code "24") (name "MEM02") (class "Default")
      (node (ref "E2") (pin "13") (pinfunction "I/O2_13") (pintype "tri_state"))
      (node (ref "E2A") (pin "13") (pinfunction "I/O2_13") (pintype "bidirectional"))
      (node (ref "E4") (pin "3") (pinfunction "O_3") (pintype "open_collector"))
      (node (ref "E4") (pin "4") (pinfunction "I0_4") (pintype "input"))
      (node (ref "RN1") (pin "4") (pinfunction "4_4") (pintype "passive"))
    )
    (net (code "25") (name "MEM03") (class "Default")
      (node (ref "E2") (pin "15") (pinfunction "I/O3_15") (pintype "tri_state"))
      (node (ref "E2A") (pin "15") (pinfunction "I/O3_15") (pintype "bidirectional"))
      (node (ref "E4") (pin "11") (pinfunction "O_11") (pintype "open_collector"))
      (node (ref "E4") (pin "9") (pinfunction "I0_9") (pintype "input"))
      (node (ref "RN1") (pin "2") (pinfunction "2_2") (pintype "passive"))
    )
    (net (code "26") (name "MEM04") (class "Default")
      (node (ref "E10") (pin "3") (pinfunction "O_3") (pintype "open_collector"))
      (node (ref "E10") (pin "4") (pinfunction "I0_4") (pintype "input"))
      (node (ref "E5") (pin "16") (pinfunction "I/O4_16") (pintype "tri_state"))
      (node (ref "E5A") (pin "16") (pinfunction "I/O4_16") (pintype "bidirectional"))
      (node (ref "RN2") (pin "3") (pinfunction "3_3") (pintype "passive"))
    )
    (net (code "27") (name "MEM05") (class "Default")
      (node (ref "E10") (pin "11") (pinfunction "O_11") (pintype "open_collector"))
      (node (ref "E10") (pin "9") (pinfunction "I0_9") (pintype "input"))
      (node (ref "E5") (pin "17") (pinfunction "I/O5_17") (pintype "tri_state"))
      (node (ref "E5A") (pin "17") (pinfunction "I/O5_17") (pintype "bidirectional"))
      (node (ref "RN2") (pin "4") (pinfunction "4_4") (pintype "passive"))
    )
    (net (code "28") (name "MEM06") (class "Default")
      (node (ref "E11") (pin "3") (pinfunction "O_3") (pintype "open_collector"))
      (node (ref "E11") (pin "4") (pinfunction "I0_4") (pintype "input"))
      (node (ref "E5") (pin "18") (pinfunction "I/O6_18") (pintype "tri_state"))
      (node (ref "E5A") (pin "18") (pinfunction "I/O6_18") (pintype "bidirectional"))
      (node (ref "RN2") (pin "6") (pinfunction "6_6") (pintype "passive"))
    )
    (net (code "29") (name "MEM07") (class "Default")
      (node (ref "E11") (pin "11") (pinfunction "O_11") (pintype "open_collector"))
      (node (ref "E11") (pin "9") (pinfunction "I0_9") (pintype "input"))
      (node (ref "E5") (pin "19") (pinfunction "I/O7_19") (pintype "tri_state"))
      (node (ref "E5A") (pin "19") (pinfunction "I/O7_19") (pintype "bidirectional"))
      (node (ref "RN2") (pin "8") (pinfunction "8_8") (pintype "passive"))
    )
    (net (code "30") (name "MEM08") (class "Default")
      (node (ref "E12") (pin "3") (pinfunction "O_3") (pintype "open_collector"))
      (node (ref "E12") (pin "4") (pinfunction "I0_4") (pintype "input"))
      (node (ref "E5") (pin "15") (pinfunction "I/O3_15") (pintype "tri_state"))
      (node (ref "E5A") (pin "15") (pinfunction "I/O3_15") (pintype "bidirectional"))
      (node (ref "RN2") (pin "2") (pinfunction "2_2") (pintype "passive"))
    )
    (net (code "31") (name "MEM09") (class "Default")
      (node (ref "E12") (pin "11") (pinfunction "O_11") (pintype "open_collector"))
      (node (ref "E12") (pin "9") (pinfunction "I0_9") (pintype "input"))
      (node (ref "E5") (pin "13") (pinfunction "I/O2_13") (pintype "tri_state"))
      (node (ref "E5A") (pin "13") (pinfunction "I/O2_13") (pintype "bidirectional"))
      (node (ref "RN2") (pin "5") (pinfunction "5_5") (pintype "passive"))
    )
    (net (code "32") (name "MEM10") (class "Default")
      (node (ref "E13") (pin "3") (pinfunction "O_3") (pintype "open_collector"))
      (node (ref "E13") (pin "4") (pinfunction "I0_4") (pintype "input"))
      (node (ref "E5") (pin "12") (pinfunction "I/O1_12") (pintype "tri_state"))
      (node (ref "E5A") (pin "12") (pinfunction "I/O1_12") (pintype "bidirectional"))
      (node (ref "RN2") (pin "7") (pinfunction "7_7") (pintype "passive"))
    )
    (net (code "33") (name "MEM11") (class "Default")
      (node (ref "E13") (pin "11") (pinfunction "O_11") (pintype "open_collector"))
      (node (ref "E13") (pin "9") (pinfunction "I0_9") (pintype "input"))
      (node (ref "E5") (pin "11") (pinfunction "I/O0_11") (pintype "tri_state"))
      (node (ref "E5A") (pin "11") (pinfunction "I/O0_11") (pintype "bidirectional"))
      (node (ref "RN2") (pin "9") (pinfunction "9_9") (pintype "passive"))
    )
    (net (code "34") (name "MEM12") (class "Default")
      (node (ref "E2") (pin "16") (pinfunction "I/O4_16") (pintype "tri_state"))
      (node (ref "E2A") (pin "16") (pinfunction "I/O4_16") (pintype "bidirectional"))
      (node (ref "RN1") (pin "3") (pinfunction "3_3") (pintype "passive"))
    )
    (net (code "35") (name "MEM13") (class "Default")
      (node (ref "E2") (pin "17") (pinfunction "I/O5_17") (pintype "tri_state"))
      (node (ref "E2A") (pin "17") (pinfunction "I/O5_17") (pintype "bidirectional"))
      (node (ref "RN1") (pin "5") (pinfunction "5_5") (pintype "passive"))
    )
    (net (code "36") (name "MEM14") (class "Default")
      (node (ref "E2") (pin "18") (pinfunction "I/O6_18") (pintype "tri_state"))
      (node (ref "E2A") (pin "18") (pinfunction "I/O6_18") (pintype "bidirectional"))
      (node (ref "RN1") (pin "7") (pinfunction "7_7") (pintype "passive"))
    )
    (net (code "37") (name "MEM15") (class "Default")
      (node (ref "E2") (pin "19") (pinfunction "I/O7_19") (pintype "tri_state"))
      (node (ref "E2A") (pin "19") (pinfunction "I/O7_19") (pintype "bidirectional"))
      (node (ref "RN1") (pin "9") (pinfunction "9_9") (pintype "passive"))
    )
    (net (code "38") (name "Net-(B1-+-Pad+@1)") (class "Default")
      (node (ref "B1") (pin "+") (pinfunction "+_+") (pintype "passive"))
      (node (ref "B1") (pin "+@1") (pinfunction "+_+@1") (pintype "passive"))
      (node (ref "B1") (pin "+@2") (pinfunction "+_+@2") (pintype "passive"))
      (node (ref "B1") (pin "+@3") (pinfunction "+_+@3") (pintype "passive"))
      (node (ref "B1") (pin "+@4") (pinfunction "+_+@4") (pintype "passive"))
      (node (ref "D2") (pin "A") (pinfunction "A_A") (pintype "passive"))
    )
    (net (code "39") (name "Net-(E9A-D0)") (class "Default")
      (node (ref "E9") (pin "4") (pinfunction "D0_4") (pintype "input"))
      (node (ref "R23") (pin "1") (pinfunction "1_1") (pintype "passive"))
      (node (ref "S1") (pin "8") (pinfunction "8_8") (pintype "passive"))
    )
    (net (code "40") (name "Net-(E9A-D1)") (class "Default")
      (node (ref "E9") (pin "3") (pinfunction "D1_3") (pintype "input"))
      (node (ref "R23") (pin "2") (pinfunction "1_2") (pintype "passive"))
      (node (ref "S1") (pin "7") (pinfunction "7_7") (pintype "passive"))
    )
    (net (code "41") (name "Net-(E9A-D2)") (class "Default")
      (node (ref "E9") (pin "2") (pinfunction "D2_2") (pintype "input"))
      (node (ref "R23") (pin "3") (pinfunction "1_3") (pintype "passive"))
      (node (ref "S1") (pin "6") (pinfunction "6_6") (pintype "passive"))
    )
    (net (code "42") (name "Net-(E9A-D3)") (class "Default")
      (node (ref "E9") (pin "1") (pinfunction "D3_1") (pintype "input"))
      (node (ref "R23") (pin "4") (pinfunction "1_4") (pintype "passive"))
      (node (ref "S1") (pin "5") (pinfunction "5_5") (pintype "passive"))
    )
    (net (code "43") (name "Net-(E9A-D4)") (class "Default")
      (node (ref "E9") (pin "15") (pinfunction "D4_15") (pintype "input"))
      (node (ref "R23") (pin "5") (pinfunction "1_5") (pintype "passive"))
      (node (ref "S1") (pin "4") (pinfunction "4_4") (pintype "passive"))
    )
    (net (code "44") (name "Net-(E9A-D5)") (class "Default")
      (node (ref "E9") (pin "14") (pinfunction "D5_14") (pintype "input"))
      (node (ref "R23") (pin "6") (pinfunction "1_6") (pintype "passive"))
      (node (ref "S1") (pin "3") (pinfunction "3_3") (pintype "passive"))
    )
    (net (code "45") (name "Net-(E9A-D6)") (class "Default")
      (node (ref "E9") (pin "13") (pinfunction "D6_13") (pintype "input"))
      (node (ref "R23") (pin "7") (pinfunction "1_7") (pintype "passive"))
      (node (ref "S1") (pin "2") (pinfunction "2_2") (pintype "passive"))
    )
    (net (code "46") (name "Net-(E9A-D7)") (class "Default")
      (node (ref "E9") (pin "12") (pinfunction "D7_12") (pintype "input"))
      (node (ref "R23") (pin "8") (pinfunction "1_8") (pintype "passive"))
      (node (ref "S1") (pin "1") (pinfunction "1_1") (pintype "passive"))
    )
    (net (code "47") (name "Net-(Q1-B)") (class "Default")
      (node (ref "Q1") (pin "2") (pinfunction "B_2") (pintype "passive"))
      (node (ref "R10") (pin "2") (pinfunction "2_2") (pintype "passive"))
    )
    (net (code "48") (name "Net-(Q1-C)") (class "Default")
      (node (ref "Q1") (pin "3") (pinfunction "C_3") (pintype "passive"))
      (node (ref "R5") (pin "1") (pinfunction "1_1") (pintype "passive"))
    )
    (net (code "49") (name "Net-(Q2-B)") (class "Default")
      (node (ref "Q2") (pin "2") (pinfunction "B_2") (pintype "passive"))
      (node (ref "R11") (pin "2") (pinfunction "2_2") (pintype "passive"))
    )
    (net (code "50") (name "Net-(Q2-C)") (class "Default")
      (node (ref "Q2") (pin "3") (pinfunction "C_3") (pintype "passive"))
      (node (ref "R6") (pin "1") (pinfunction "1_1") (pintype "passive"))
    )
    (net (code "51") (name "Net-(Q3-B)") (class "Default")
      (node (ref "Q3") (pin "2") (pinfunction "B_2") (pintype "passive"))
      (node (ref "R24") (pin "2") (pinfunction "2_2") (pintype "passive"))
    )
    (net (code "52") (name "Net-(SW2-S)") (class "Default")
      (node (ref "R12") (pin "2") (pinfunction "2_2") (pintype "passive"))
      (node (ref "SW2") (pin "1") (pinfunction "S_1") (pintype "passive"))
      (node (ref "SW2") (pin "2") (pinfunction "S1_2") (pintype "passive"))
    )
    (net (code "53") (name "Net-(SW3A-2)") (class "Default")
      (node (ref "R9") (pin "2") (pinfunction "2_2") (pintype "passive"))
      (node (ref "SW3") (pin "8") (pinfunction "2_8") (pintype "passive"))
    )
    (net (code "54") (name "Net-(SW3B-2)") (class "Default")
      (node (ref "R8") (pin "2") (pinfunction "2_2") (pintype "passive"))
      (node (ref "SW3") (pin "7") (pinfunction "2_7") (pintype "passive"))
    )
    (net (code "55") (name "Net-(SW3C-2)") (class "Default")
      (node (ref "R4") (pin "2") (pinfunction "2_2") (pintype "passive"))
      (node (ref "SW3") (pin "6") (pinfunction "2_6") (pintype "passive"))
    )
    (net (code "56") (name "Net-(SW3D-2)") (class "Default")
      (node (ref "R3") (pin "2") (pinfunction "2_2") (pintype "passive"))
      (node (ref "SW3") (pin "5") (pinfunction "2_5") (pintype "passive"))
    )
    (net (code "57") (name "Net-(U1-PB6(XTAL1{slash}TOSC1))") (class "Default")
      (node (ref "C9") (pin "1") (pinfunction "1_1") (pintype "passive"))
      (node (ref "R18") (pin "1") (pinfunction "1_1") (pintype "passive"))
      (node (ref "U1") (pin "9") (pinfunction "PB6(XTAL1/TOSC1)_9") (pintype "bidirectional"))
      (node (ref "Y1") (pin "2") (pinfunction "2_2") (pintype "passive"))
    )
    (net (code "58") (name "Net-(U1-PB7(XTAL2{slash}TOSC2))") (class "Default")
      (node (ref "C7") (pin "1") (pinfunction "1_1") (pintype "passive"))
      (node (ref "R18") (pin "2") (pinfunction "2_2") (pintype "passive"))
      (node (ref "U1") (pin "10") (pinfunction "PB7(XTAL2/TOSC2)_10") (pintype "bidirectional"))
      (node (ref "Y1") (pin "1") (pinfunction "1_1") (pintype "passive"))
    )
    (net (code "59") (name "Net-(U1-PD0(RXD))") (class "Default")
      (node (ref "R16") (pin "1") (pinfunction "1_1") (pintype "passive"))
      (node (ref "U1") (pin "2") (pinfunction "PD0(RXD)_2") (pintype "bidirectional"))
    )
    (net (code "60") (name "Net-(U1-PD1(TXD))") (class "Default")
      (node (ref "R17") (pin "1") (pinfunction "1_1") (pintype "passive"))
      (node (ref "U1") (pin "3") (pinfunction "PD1(TXD)_3") (pintype "bidirectional"))
    )
    (net (code "61") (name "Net-(U8A-O)") (class "Default")
      (node (ref "U8") (pin "12") (pinfunction "O_12") (pintype "output"))
      (node (ref "U8") (pin "3") (pinfunction "I0_3") (pintype "input"))
      (node (ref "U8") (pin "4") (pinfunction "I1_4") (pintype "input"))
      (node (ref "U8") (pin "5") (pinfunction "I2_5") (pintype "input"))
    )
    (net (code "62") (name "Net-(U8C-I0)") (class "Default")
      (node (ref "U8") (pin "9") (pinfunction "I0_9") (pintype "input"))
      (node (ref "U9") (pin "8") (pinfunction "O_8") (pintype "output"))
    )
    (net (code "63") (name "Net-(U8C-I1)") (class "Default")
      (node (ref "U8") (pin "10") (pinfunction "I1_10") (pintype "input"))
      (node (ref "U9") (pin "6") (pinfunction "O_6") (pintype "output"))
    )
    (net (code "64") (name "Net-(U8C-O)") (class "Default")
      (node (ref "U8") (pin "8") (pinfunction "O_8") (pintype "output"))
      (node (ref "U9") (pin "13") (pinfunction "I1_13") (pintype "input"))
      (node (ref "U9") (pin "2") (pinfunction "I1_2") (pintype "input"))
    )
    (net (code "65") (name "Net-(U9A-O)") (class "Default")
      (node (ref "U9") (pin "12") (pinfunction "I0_12") (pintype "input"))
      (node (ref "U9") (pin "3") (pinfunction "O_3") (pintype "output"))
    )
    (net (code "66") (name "Net-(U10A-C1+)") (class "Default")
      (node (ref "C14") (pin "1") (pinfunction "1_1") (pintype "passive"))
      (node (ref "U10") (pin "1") (pinfunction "C1+_1") (pintype "bidirectional"))
    )
    (net (code "67") (name "Net-(U10A-C1-)") (class "Default")
      (node (ref "C14") (pin "2") (pinfunction "2_2") (pintype "passive"))
      (node (ref "U10") (pin "3") (pinfunction "C1-_3") (pintype "bidirectional"))
    )
    (net (code "68") (name "Net-(U10A-C2+)") (class "Default")
      (node (ref "C15") (pin "1") (pinfunction "1_1") (pintype "passive"))
      (node (ref "U10") (pin "4") (pinfunction "C2+_4") (pintype "bidirectional"))
    )
    (net (code "69") (name "Net-(U10A-C2-)") (class "Default")
      (node (ref "C15") (pin "2") (pinfunction "2_2") (pintype "passive"))
      (node (ref "U10") (pin "5") (pinfunction "C2-_5") (pintype "bidirectional"))
    )
    (net (code "70") (name "Net-(U10A-V+)") (class "Default")
      (node (ref "C16") (pin "1") (pinfunction "1_1") (pintype "passive"))
      (node (ref "U10") (pin "2") (pinfunction "V+_2") (pintype "bidirectional"))
    )
    (net (code "71") (name "Net-(U10A-V-)") (class "Default")
      (node (ref "C17") (pin "2") (pinfunction "2_2") (pintype "passive"))
      (node (ref "U10") (pin "6") (pinfunction "V-_6") (pintype "bidirectional"))
    )
    (net (code "72") (name "OE") (class "Default")
      (node (ref "E10") (pin "10") (pinfunction "I1_10") (pintype "input"))
      (node (ref "E10") (pin "5") (pinfunction "I1_5") (pintype "input"))
      (node (ref "E11") (pin "10") (pinfunction "I1_10") (pintype "input"))
      (node (ref "E11") (pin "5") (pinfunction "I1_5") (pintype "input"))
      (node (ref "E12") (pin "10") (pinfunction "I1_10") (pintype "input"))
      (node (ref "E12") (pin "5") (pinfunction "I1_5") (pintype "input"))
      (node (ref "E13") (pin "10") (pinfunction "I1_10") (pintype "input"))
      (node (ref "E13") (pin "5") (pinfunction "I1_5") (pintype "input"))
      (node (ref "E3") (pin "10") (pinfunction "I1_10") (pintype "input"))
      (node (ref "E3") (pin "5") (pinfunction "I1_5") (pintype "input"))
      (node (ref "E4") (pin "10") (pinfunction "I1_10") (pintype "input"))
      (node (ref "E4") (pin "5") (pinfunction "I1_5") (pintype "input"))
      (node (ref "E6") (pin "12") (pinfunction "Y7_12") (pintype "tri_state"))
    )
    (net (code "73") (name "POWER_OK") (class "Default")
      (node (ref "E14") (pin "39") (pinfunction "IO28_39") (pintype "bidirectional"))
      (node (ref "J1") (pin "BV2") (pinfunction "1_BV2") (pintype "bidirectional"))
      (node (ref "R24") (pin "1") (pinfunction "1_1") (pintype "passive"))
    )
    (net (code "74") (name "PROG") (class "Default")
      (node (ref "C11") (pin "2") (pinfunction "2_2") (pintype "passive"))
      (node (ref "J2") (pin "1") (pinfunction "1_1") (pintype "passive"))
      (node (ref "R20") (pin "2") (pinfunction "2_2") (pintype "passive"))
      (node (ref "SV1") (pin "1") (pinfunction "1_1") (pintype "passive"))
    )
    (net (code "75") (name "PULSE_LA") (class "Default")
      (node (ref "E14") (pin "2") (pinfunction "IN/GCLK2/OE2_2") (pintype "input"))
      (node (ref "J1") (pin "DR2") (pinfunction "1_DR2") (pintype "bidirectional"))
      (node (ref "Q2") (pin "1") (pinfunction "E_1") (pintype "passive"))
    )
    (net (code "76") (name "RETURN") (class "Default")
      (node (ref "J1") (pin "AR2") (pinfunction "1_AR2") (pintype "bidirectional"))
    )
    (net (code "77") (name "ROM_ADDR") (class "Default")
      (node (ref "E6") (pin "11") (pinfunction "Y8_11") (pintype "tri_state"))
      (node (ref "E9") (pin "7") (pinfunction "G_7") (pintype "input"))
    )
    (net (code "78") (name "RXD") (class "Default")
      (node (ref "J2") (pin "2") (pinfunction "2_2") (pintype "passive"))
      (node (ref "R16") (pin "2") (pinfunction "2_2") (pintype "passive"))
      (node (ref "SV1") (pin "3") (pinfunction "3_3") (pintype "passive"))
    )
    (net (code "79") (name "RXD232") (class "Default")
      (node (ref "J4") (pin "J") (pinfunction "8_J") (pintype "bidirectional"))
      (node (ref "J5") (pin "2") (pinfunction "F_2") (pintype "passive"))
      (node (ref "U10") (pin "8") (pinfunction "R2IN_8") (pintype "input"))
    )
    (net (code "80") (name "RXDTTL") (class "Default")
      (node (ref "E14") (pin "75") (pinfunction "IO55_75") (pintype "bidirectional"))
      (node (ref "SV1") (pin "4") (pinfunction "4_4") (pintype "passive"))
      (node (ref "U10") (pin "9") (pinfunction "R2OUT_9") (pintype "output"))
    )
    (net (code "81") (name "R_RUN") (class "Default")
      (node (ref "R2") (pin "1") (pinfunction "1_1") (pintype "passive"))
      (node (ref "U1") (pin "14") (pinfunction "PB0(ICP)_14") (pintype "bidirectional"))
    )
    (net (code "82") (name "R_SW") (class "Default")
      (node (ref "C10") (pin "1") (pinfunction "1_1") (pintype "passive"))
      (node (ref "R1") (pin "1") (pinfunction "1_1") (pintype "passive"))
      (node (ref "R12") (pin "1") (pinfunction "1_1") (pintype "passive"))
      (node (ref "U1") (pin "15") (pinfunction "PB1(OC1A)_15") (pintype "bidirectional"))
    )
    (net (code "83") (name "SCL") (class "Default")
      (node (ref "R22") (pin "1") (pinfunction "1_1") (pintype "passive"))
      (node (ref "U1") (pin "28") (pinfunction "PC5(ADC5/SCL)_28") (pintype "bidirectional"))
      (node (ref "U11") (pin "6") (pinfunction "SCL_6") (pintype "input"))
      (node (ref "U2") (pin "12") (pinfunction "SCL_12") (pintype "input"))
    )
    (net (code "84") (name "SDA") (class "Default")
      (node (ref "R21") (pin "1") (pinfunction "1_1") (pintype "passive"))
      (node (ref "U1") (pin "27") (pinfunction "PC4(ADC4/SDA)_27") (pintype "bidirectional"))
      (node (ref "U11") (pin "5") (pinfunction "SDA_5") (pintype "bidirectional"))
      (node (ref "U2") (pin "13") (pinfunction "SDA_13") (pintype "bidirectional"))
    )
    (net (code "85") (name "SET_FF") (class "Default")
      (node (ref "U1") (pin "4") (pinfunction "PD2(INT0)_4") (pintype "bidirectional"))
      (node (ref "U9") (pin "1") (pinfunction "I0_1") (pintype "input"))
    )
    (net (code "86") (name "SHOW_DATA") (class "Default")
      (node (ref "U1") (pin "5") (pinfunction "PD3(INT1)_5") (pintype "bidirectional"))
      (node (ref "U8") (pin "1") (pinfunction "I0_1") (pintype "input"))
    )
    (net (code "87") (name "SOURCE") (class "Default")
      (node (ref "E6") (pin "3") (pinfunction "A2_3") (pintype "input"))
      (node (ref "J1") (pin "AL2") (pinfunction "1_AL2") (pintype "bidirectional"))
    )
    (net (code "88") (name "STROBE") (class "Default")
      (node (ref "J1") (pin "AM2") (pinfunction "1_AM2") (pintype "bidirectional"))
    )
    (net (code "89") (name "SW") (class "Default")
      (node (ref "J1") (pin "DV2") (pinfunction "1_DV2") (pintype "bidirectional"))
      (node (ref "R1") (pin "2") (pinfunction "2_2") (pintype "passive"))
    )
    (net (code "90") (name "TCK2") (class "Default")
      (node (ref "E14") (pin "62") (pinfunction "TCK_62") (pintype "bidirectional"))
      (node (ref "SV2") (pin "1") (pinfunction "1_1") (pintype "passive"))
    )
    (net (code "91") (name "TDI2") (class "Default")
      (node (ref "E14") (pin "14") (pinfunction "TDI_14") (pintype "bidirectional"))
      (node (ref "SV2") (pin "9") (pinfunction "9_9") (pintype "passive"))
    )
    (net (code "92") (name "TDO2") (class "Default")
      (node (ref "E14") (pin "71") (pinfunction "TDO_71") (pintype "bidirectional"))
      (node (ref "SV2") (pin "3") (pinfunction "3_3") (pintype "passive"))
    )
    (net (code "93") (name "TMS2") (class "Default")
      (node (ref "E14") (pin "23") (pinfunction "TMS_23") (pintype "bidirectional"))
      (node (ref "SV2") (pin "5") (pinfunction "5_5") (pintype "passive"))
    )
    (net (code "94") (name "TP1") (class "Default")
      (node (ref "J1") (pin "CD2") (pinfunction "1_CD2") (pintype "bidirectional"))
    )
    (net (code "95") (name "TP2") (class "Default")
      (node (ref "E14") (pin "34") (pinfunction "IO24_34") (pintype "bidirectional"))
      (node (ref "J1") (pin "CE2") (pinfunction "1_CE2") (pintype "bidirectional"))
    )
    (net (code "96") (name "TP3") (class "Default")
      (node (ref "E14") (pin "31") (pinfunction "IO22_31") (pintype "bidirectional"))
      (node (ref "J1") (pin "CH2") (pinfunction "1_CH2") (pintype "bidirectional"))
    )
    (net (code "97") (name "TP4") (class "Default")
      (node (ref "E14") (pin "30") (pinfunction "IO21_30") (pintype "bidirectional"))
      (node (ref "E6") (pin "2") (pinfunction "A1_2") (pintype "input"))
      (node (ref "J1") (pin "CJ2") (pinfunction "1_CJ2") (pintype "bidirectional"))
      (node (ref "U9") (pin "4") (pinfunction "I0_4") (pintype "input"))
      (node (ref "U9") (pin "5") (pinfunction "I1_5") (pintype "input"))
    )
    (net (code "98") (name "TP_AA1") (class "Default")
      (node (ref "E14") (pin "74") (pinfunction "IO54_74") (pintype "bidirectional"))
      (node (ref "J1") (pin "AA1") (pinfunction "1_AA1") (pintype "bidirectional"))
      (node (ref "RN3") (pin "4") (pinfunction "4_4") (pintype "passive"))
      (node (ref "SERIAL") (pin "10") (pinfunction "10_10") (pintype "passive"))
    )
    (net (code "99") (name "TP_AB1") (class "Default")
      (node (ref "E14") (pin "73") (pinfunction "IO53_73") (pintype "bidirectional"))
      (node (ref "J1") (pin "AB1") (pinfunction "1_AB1") (pintype "bidirectional"))
      (node (ref "RN3") (pin "5") (pinfunction "5_5") (pintype "passive"))
      (node (ref "SERIAL") (pin "9") (pinfunction "9_9") (pintype "passive"))
    )
    (net (code "100") (name "TP_BA1") (class "Default")
      (node (ref "E14") (pin "56") (pinfunction "IO41_56") (pintype "bidirectional"))
      (node (ref "J1") (pin "BA1") (pinfunction "1_BA1") (pintype "bidirectional"))
      (node (ref "RN3") (pin "6") (pinfunction "6_6") (pintype "passive"))
      (node (ref "SERIAL") (pin "8") (pinfunction "8_8") (pintype "passive"))
    )
    (net (code "101") (name "TP_BB1") (class "Default")
      (node (ref "E14") (pin "55") (pinfunction "IO40_55") (pintype "bidirectional"))
      (node (ref "J1") (pin "BB1") (pinfunction "1_BB1") (pintype "bidirectional"))
      (node (ref "RN3") (pin "7") (pinfunction "7_7") (pintype "passive"))
      (node (ref "SERIAL") (pin "7") (pinfunction "7_7") (pintype "passive"))
    )
    (net (code "102") (name "TXD") (class "Default")
      (node (ref "J2") (pin "3") (pinfunction "3_3") (pintype "passive"))
      (node (ref "R17") (pin "2") (pinfunction "2_2") (pintype "passive"))
      (node (ref "SV1") (pin "5") (pinfunction "5_5") (pintype "passive"))
    )
    (net (code "103") (name "TXD232") (class "Default")
      (node (ref "J4") (pin "F") (pinfunction "6_F") (pintype "bidirectional"))
      (node (ref "J5") (pin "3") (pinfunction "F_3") (pintype "passive"))
      (node (ref "U10") (pin "7") (pinfunction "T2OUT_7") (pintype "output"))
    )
    (net (code "104") (name "TXDTTL") (class "Default")
      (node (ref "E14") (pin "76") (pinfunction "IO56_76") (pintype "bidirectional"))
      (node (ref "SV1") (pin "6") (pinfunction "6_6") (pintype "passive"))
      (node (ref "U10") (pin "10") (pinfunction "T2IN_10") (pintype "input"))
    )
    (net (code "105") (name "V+") (class "Default")
      (node (ref "C20") (pin "1") (pinfunction "1_1") (pintype "passive"))
      (node (ref "C21") (pin "1") (pinfunction "1_1") (pintype "passive"))
      (node (ref "D2") (pin "C") (pinfunction "C_C") (pintype "passive"))
      (node (ref "D3") (pin "C") (pinfunction "C_C") (pintype "passive"))
      (node (ref "E2") (pin "28") (pinfunction "VCC_28") (pintype "power_in"))
      (node (ref "E2A") (pin "28") (pinfunction "VCC_28") (pintype "power_in"))
      (node (ref "E5") (pin "28") (pinfunction "VCC_28") (pintype "power_in"))
      (node (ref "E5A") (pin "28") (pinfunction "VCC_28") (pintype "power_in"))
      (node (ref "R15") (pin "2") (pinfunction "2_2") (pintype "passive"))
    )
    (net (code "106") (name "VCC") (class "Default")
      (node (ref "C1") (pin "1") (pinfunction "1_1") (pintype "passive"))
      (node (ref "C12") (pin "1") (pinfunction "1_1") (pintype "passive"))
      (node (ref "C13") (pin "1") (pinfunction "1_1") (pintype "passive"))
      (node (ref "C16") (pin "2") (pinfunction "2_2") (pintype "passive"))
      (node (ref "C18") (pin "1") (pinfunction "1_1") (pintype "passive"))
      (node (ref "C19") (pin "1") (pinfunction "1_1") (pintype "passive"))
      (node (ref "C2") (pin "1") (pinfunction "1_1") (pintype "passive"))
      (node (ref "C23") (pin "1") (pinfunction "1_1") (pintype "passive"))
      (node (ref "C24") (pin "1") (pinfunction "1_1") (pintype "passive"))
      (node (ref "C25") (pin "1") (pinfunction "1_1") (pintype "passive"))
      (node (ref "C26") (pin "1") (pinfunction "1_1") (pintype "passive"))
      (node (ref "C27") (pin "1") (pinfunction "1_1") (pintype "passive"))
      (node (ref "C28") (pin "1") (pinfunction "1_1") (pintype "passive"))
      (node (ref "C29") (pin "1") (pinfunction "1_1") (pintype "passive"))
      (node (ref "C3") (pin "1") (pinfunction "1_1") (pintype "passive"))
      (node (ref "C30") (pin "+") (pinfunction "+_+") (pintype "passive"))
      (node (ref "C31") (pin "1") (pinfunction "1_1") (pintype "passive"))
      (node (ref "C32") (pin "1") (pinfunction "1_1") (pintype "passive"))
      (node (ref "C33") (pin "1") (pinfunction "1_1") (pintype "passive"))
      (node (ref "C34") (pin "+") (pinfunction "+_+") (pintype "passive"))
      (node (ref "C35") (pin "+") (pinfunction "+_+") (pintype "passive"))
      (node (ref "C36") (pin "1") (pinfunction "1_1") (pintype "passive"))
      (node (ref "C37") (pin "1") (pinfunction "1_1") (pintype "passive"))
      (node (ref "C4") (pin "1") (pinfunction "1_1") (pintype "passive"))
      (node (ref "C45") (pin "1") (pinfunction "1_1") (pintype "passive"))
      (node (ref "C5") (pin "1") (pinfunction "1_1") (pintype "passive"))
      (node (ref "C6") (pin "1") (pinfunction "1_1") (pintype "passive"))
      (node (ref "C8") (pin "1") (pinfunction "1_1") (pintype "passive"))
      (node (ref "D1") (pin "C") (pinfunction "C_C") (pintype "passive"))
      (node (ref "D3") (pin "A") (pinfunction "A_A") (pintype "passive"))
      (node (ref "J1") (pin "AA2") (pinfunction "1_AA2") (pintype "bidirectional"))
      (node (ref "J1") (pin "BA2") (pinfunction "1_BA2") (pintype "bidirectional"))
      (node (ref "J1") (pin "CA2") (pinfunction "1_CA2") (pintype "bidirectional"))
      (node (ref "J3") (pin "2") (pinfunction "2_2") (pintype "passive"))
      (node (ref "OSC") (pin "8") (pinfunction "VCC_8") (pintype "power_in"))
      (node (ref "OSC1") (pin "14") (pinfunction "VCC_14") (pintype "power_in"))
      (node (ref "R13") (pin "2") (pinfunction "2_2") (pintype "passive"))
      (node (ref "R14") (pin "2") (pinfunction "2_2") (pintype "passive"))
      (node (ref "R19") (pin "2") (pinfunction "2_2") (pintype "passive"))
      (node (ref "R21") (pin "2") (pinfunction "2_2") (pintype "passive"))
      (node (ref "R22") (pin "2") (pinfunction "2_2") (pintype "passive"))
      (node (ref "R23") (pin "10") (pinfunction "2_10") (pintype "passive"))
      (node (ref "R23") (pin "11") (pinfunction "2_11") (pintype "passive"))
      (node (ref "R23") (pin "12") (pinfunction "2_12") (pintype "passive"))
      (node (ref "R23") (pin "13") (pinfunction "2_13") (pintype "passive"))
      (node (ref "R23") (pin "14") (pinfunction "2_14") (pintype "passive"))
      (node (ref "R23") (pin "15") (pinfunction "2_15") (pintype "passive"))
      (node (ref "R23") (pin "16") (pinfunction "2_16") (pintype "passive"))
      (node (ref "R23") (pin "9") (pinfunction "2_9") (pintype "passive"))
      (node (ref "R5") (pin "2") (pinfunction "2_2") (pintype "passive"))
      (node (ref "R6") (pin "2") (pinfunction "2_2") (pintype "passive"))
      (node (ref "RN1") (pin "1") (pinfunction "1_1") (pintype "passive"))
      (node (ref "RN2") (pin "1") (pinfunction "1_1") (pintype "passive"))
      (node (ref "RN3") (pin "1") (pinfunction "1_1") (pintype "passive"))
      (node (ref "SV2") (pin "4") (pinfunction "4_4") (pintype "passive"))
      (node (ref "U1") (pin "20") (pinfunction "AVCC_20") (pintype "power_in"))
      (node (ref "U1") (pin "21") (pinfunction "AREF_21") (pintype "passive"))
      (node (ref "U1") (pin "7") (pinfunction "VCC_7") (pintype "power_in"))
      (node (ref "U11") (pin "8") (pinfunction "VCC_8") (pintype "power_in"))
      (node (ref "U2") (pin "18") (pinfunction "~{RESET}_18") (pintype "input"))
      (node (ref "U2") (pin "9") (pinfunction "VDD_9") (pintype "power_in"))
      (node (ref "U7") (pin "12") (pinfunction "I0_12") (pintype "input"))
      (node (ref "U7") (pin "13") (pinfunction "I1_13") (pintype "input"))
      (node (ref "VCCINT") (pin "1") (pinfunction "1_1") (pintype "bidirectional"))
      (node (ref "VCCIO") (pin "1") (pinfunction "1_1") (pintype "bidirectional"))
    )
    (net (code "107") (name "VCCINT") (class "Default")
      (node (ref "C41") (pin "1") (pinfunction "1_1") (pintype "passive"))
      (node (ref "C43") (pin "1") (pinfunction "1_1") (pintype "passive"))
      (node (ref "VCCINT") (pin "2") (pinfunction "2_2") (pintype "bidirectional"))
    )
    (net (code "108") (name "VCCIO") (class "Default")
      (node (ref "C42") (pin "1") (pinfunction "1_1") (pintype "passive"))
      (node (ref "C44") (pin "1") (pinfunction "1_1") (pintype "passive"))
      (node (ref "VCCIO") (pin "2") (pinfunction "2_2") (pintype "bidirectional"))
    )
    (net (code "109") (name "WE") (class "Default")
      (node (ref "E10") (pin "13") (pinfunction "I1_13") (pintype "input"))
      (node (ref "E10") (pin "2") (pinfunction "I1_2") (pintype "input"))
      (node (ref "E11") (pin "13") (pinfunction "I1_13") (pintype "input"))
      (node (ref "E11") (pin "2") (pinfunction "I1_2") (pintype "input"))
      (node (ref "E12") (pin "13") (pinfunction "I1_13") (pintype "input"))
      (node (ref "E12") (pin "2") (pinfunction "I1_2") (pintype "input"))
      (node (ref "E13") (pin "13") (pinfunction "I1_13") (pintype "input"))
      (node (ref "E13") (pin "2") (pinfunction "I1_2") (pintype "input"))
      (node (ref "E3") (pin "13") (pinfunction "I1_13") (pintype "input"))
      (node (ref "E3") (pin "2") (pinfunction "I1_2") (pintype "input"))
      (node (ref "E4") (pin "13") (pinfunction "I1_13") (pintype "input"))
      (node (ref "E4") (pin "2") (pinfunction "I1_2") (pintype "input"))
      (node (ref "E6") (pin "13") (pinfunction "Y6_13") (pintype "tri_state"))
    )
    (net (code "110") (name "WRITE") (class "Default")
      (node (ref "E8") (pin "3") (pinfunction "I0_3") (pintype "input"))
      (node (ref "J1") (pin "AS2") (pinfunction "1_AS2") (pintype "bidirectional"))
    )
    (net (code "111") (name "W_DATA_00") (class "Default")
      (node (ref "U2") (pin "7") (pinfunction "GPB6_7") (pintype "bidirectional"))
      (node (ref "U3") (pin "2") (pinfunction "I1_2") (pintype "input"))
    )
    (net (code "112") (name "W_DATA_01") (class "Default")
      (node (ref "U2") (pin "6") (pinfunction "GPB5_6") (pintype "bidirectional"))
      (node (ref "U3") (pin "4") (pinfunction "I0_4") (pintype "input"))
    )
    (net (code "113") (name "W_DATA_02") (class "Default")
      (node (ref "U2") (pin "5") (pinfunction "GPB4_5") (pintype "bidirectional"))
      (node (ref "U3") (pin "12") (pinfunction "I0_12") (pintype "input"))
    )
    (net (code "114") (name "W_DATA_03") (class "Default")
      (node (ref "U2") (pin "3") (pinfunction "GPB2_3") (pintype "bidirectional"))
      (node (ref "U3") (pin "9") (pinfunction "I0_9") (pintype "input"))
    )
    (net (code "115") (name "W_DATA_04") (class "Default")
      (node (ref "U2") (pin "2") (pinfunction "GPB1_2") (pintype "bidirectional"))
      (node (ref "U4") (pin "2") (pinfunction "I1_2") (pintype "input"))
    )
    (net (code "116") (name "W_DATA_05") (class "Default")
      (node (ref "U2") (pin "1") (pinfunction "GPB0_1") (pintype "bidirectional"))
      (node (ref "U4") (pin "4") (pinfunction "I0_4") (pintype "input"))
    )
    (net (code "117") (name "W_DATA_06") (class "Default")
      (node (ref "U2") (pin "27") (pinfunction "GPA6_27") (pintype "bidirectional"))
      (node (ref "U4") (pin "12") (pinfunction "I0_12") (pintype "input"))
    )
    (net (code "118") (name "W_DATA_07") (class "Default")
      (node (ref "U2") (pin "26") (pinfunction "GPA5_26") (pintype "bidirectional"))
      (node (ref "U4") (pin "9") (pinfunction "I0_9") (pintype "input"))
    )
    (net (code "119") (name "W_DATA_08") (class "Default")
      (node (ref "U2") (pin "25") (pinfunction "GPA4_25") (pintype "bidirectional"))
      (node (ref "U5") (pin "2") (pinfunction "I1_2") (pintype "input"))
    )
    (net (code "120") (name "W_DATA_09") (class "Default")
      (node (ref "U2") (pin "23") (pinfunction "GPA2_23") (pintype "bidirectional"))
      (node (ref "U5") (pin "4") (pinfunction "I0_4") (pintype "input"))
    )
    (net (code "121") (name "W_DATA_10") (class "Default")
      (node (ref "U2") (pin "22") (pinfunction "GPA1_22") (pintype "bidirectional"))
      (node (ref "U5") (pin "12") (pinfunction "I0_12") (pintype "input"))
    )
    (net (code "122") (name "W_DATA_11") (class "Default")
      (node (ref "U2") (pin "21") (pinfunction "GPA0_21") (pintype "bidirectional"))
      (node (ref "U5") (pin "9") (pinfunction "I0_9") (pintype "input"))
    )
    (net (code "123") (name "W_INITIALIZE") (class "Default")
      (node (ref "R10") (pin "1") (pinfunction "1_1") (pintype "passive"))
      (node (ref "R13") (pin "1") (pinfunction "1_1") (pintype "passive"))
      (node (ref "U1") (pin "23") (pinfunction "PC0(ADC0)_23") (pintype "bidirectional"))
    )
    (net (code "124") (name "W_PULSE_LA") (class "Default")
      (node (ref "R11") (pin "1") (pinfunction "1_1") (pintype "passive"))
      (node (ref "R14") (pin "1") (pinfunction "1_1") (pintype "passive"))
      (node (ref "U1") (pin "24") (pinfunction "PC1(ADC1)_24") (pintype "bidirectional"))
    )
    (net (code "125") (name "W_STOP") (class "Default")
      (node (ref "U1") (pin "26") (pinfunction "PC3(ADC3)_26") (pintype "bidirectional"))
      (node (ref "U7") (pin "10") (pinfunction "I1_10") (pintype "input"))
      (node (ref "U7") (pin "9") (pinfunction "I0_9") (pintype "input"))
    )
    (net (code "126") (name "unconnected-(E1A-Y4-Pad12)") (class "Default")
      (node (ref "E1") (pin "12") (pinfunction "Y4_12") (pintype "tri_state"))
    )
    (net (code "127") (name "unconnected-(E9A-W-Pad6)") (class "Default")
      (node (ref "E9") (pin "6") (pinfunction "W_6") (pintype "output"))
    )
    (net (code "128") (name "unconnected-(J1BN-1-PadBS2)") (class "Default")
      (node (ref "J1") (pin "BS2") (pinfunction "1_BS2") (pintype "bidirectional"))
    )
    (net (code "129") (name "unconnected-(J1BW-1-PadCB1)") (class "Default")
      (node (ref "J1") (pin "CB1") (pinfunction "1_CB1") (pintype "bidirectional"))
    )
    (net (code "130") (name "unconnected-(J1DE-1-PadDA1)") (class "Default")
      (node (ref "J1") (pin "DA1") (pinfunction "1_DA1") (pintype "bidirectional"))
    )
    (net (code "131") (name "unconnected-(J1DG-1-PadDB1)") (class "Default")
      (node (ref "J1") (pin "DB1") (pinfunction "1_DB1") (pintype "bidirectional"))
    )
    (net (code "132") (name "unconnected-(J4-3-PadC)") (class "Default")
      (node (ref "J4") (pin "C") (pinfunction "3_C") (pintype "bidirectional"))
    )
    (net (code "133") (name "unconnected-(J4-4-PadD)") (class "Default")
      (node (ref "J4") (pin "D") (pinfunction "4_D") (pintype "bidirectional"))
    )
    (net (code "134") (name "unconnected-(J4-5-PadE)") (class "Default")
      (node (ref "J4") (pin "E") (pinfunction "5_E") (pintype "bidirectional"))
    )
    (net (code "135") (name "unconnected-(J4-7-PadH)") (class "Default")
      (node (ref "J4") (pin "H") (pinfunction "7_H") (pintype "bidirectional"))
    )
    (net (code "136") (name "unconnected-(J4-9-PadK)") (class "Default")
      (node (ref "J4") (pin "K") (pinfunction "9_K") (pintype "bidirectional"))
    )
    (net (code "137") (name "unconnected-(J4-10-PadL)") (class "Default")
      (node (ref "J4") (pin "L") (pinfunction "10_L") (pintype "bidirectional"))
    )
    (net (code "138") (name "unconnected-(J4-11-PadM)") (class "Default")
      (node (ref "J4") (pin "M") (pinfunction "11_M") (pintype "bidirectional"))
    )
    (net (code "139") (name "unconnected-(J4-12-PadN)") (class "Default")
      (node (ref "J4") (pin "N") (pinfunction "12_N") (pintype "bidirectional"))
    )
    (net (code "140") (name "unconnected-(J4-13-PadP)") (class "Default")
      (node (ref "J4") (pin "P") (pinfunction "13_P") (pintype "bidirectional"))
    )
    (net (code "141") (name "unconnected-(J4-14-PadR)") (class "Default")
      (node (ref "J4") (pin "R") (pinfunction "14_R") (pintype "bidirectional"))
    )
    (net (code "142") (name "unconnected-(J4-15-PadS)") (class "Default")
      (node (ref "J4") (pin "S") (pinfunction "15_S") (pintype "bidirectional"))
    )
    (net (code "143") (name "unconnected-(J4-16-PadT)") (class "Default")
      (node (ref "J4") (pin "T") (pinfunction "16_T") (pintype "bidirectional"))
    )
    (net (code "144") (name "unconnected-(J4-17-PadU)") (class "Default")
      (node (ref "J4") (pin "U") (pinfunction "17_U") (pintype "bidirectional"))
    )
    (net (code "145") (name "unconnected-(J4-18-PadV)") (class "Default")
      (node (ref "J4") (pin "V") (pinfunction "18_V") (pintype "bidirectional"))
    )
    (net (code "146") (name "unconnected-(J4-19-PadW)") (class "Default")
      (node (ref "J4") (pin "W") (pinfunction "19_W") (pintype "bidirectional"))
    )
    (net (code "147") (name "unconnected-(J4-20-PadX)") (class "Default")
      (node (ref "J4") (pin "X") (pinfunction "20_X") (pintype "bidirectional"))
    )
    (net (code "148") (name "unconnected-(J4-21-PadY)") (class "Default")
      (node (ref "J4") (pin "Y") (pinfunction "21_Y") (pintype "bidirectional"))
    )
    (net (code "149") (name "unconnected-(J4-23-PadAA)") (class "Default")
      (node (ref "J4") (pin "AA") (pinfunction "23_AA") (pintype "bidirectional"))
    )
    (net (code "150") (name "unconnected-(J4-24-PadBB)") (class "Default")
      (node (ref "J4") (pin "BB") (pinfunction "24_BB") (pintype "bidirectional"))
    )
    (net (code "151") (name "unconnected-(J4-25-PadCC)") (class "Default")
      (node (ref "J4") (pin "CC") (pinfunction "25_CC") (pintype "bidirectional"))
    )
    (net (code "152") (name "unconnected-(J4-26-PadDD)") (class "Default")
      (node (ref "J4") (pin "DD") (pinfunction "26_DD") (pintype "bidirectional"))
    )
    (net (code "153") (name "unconnected-(J4-27-PadEE)") (class "Default")
      (node (ref "J4") (pin "EE") (pinfunction "27_EE") (pintype "bidirectional"))
    )
    (net (code "154") (name "unconnected-(J4-28-PadFF)") (class "Default")
      (node (ref "J4") (pin "FF") (pinfunction "28_FF") (pintype "bidirectional"))
    )
    (net (code "155") (name "unconnected-(J4-29-PadHH)") (class "Default")
      (node (ref "J4") (pin "HH") (pinfunction "29_HH") (pintype "bidirectional"))
    )
    (net (code "156") (name "unconnected-(J4-30-PadJJ)") (class "Default")
      (node (ref "J4") (pin "JJ") (pinfunction "30_JJ") (pintype "bidirectional"))
    )
    (net (code "157") (name "unconnected-(J4-31-PadKK)") (class "Default")
      (node (ref "J4") (pin "KK") (pinfunction "31_KK") (pintype "bidirectional"))
    )
    (net (code "158") (name "unconnected-(J4-32-PadLL)") (class "Default")
      (node (ref "J4") (pin "LL") (pinfunction "32_LL") (pintype "bidirectional"))
    )
    (net (code "159") (name "unconnected-(J4-33-PadMM)") (class "Default")
      (node (ref "J4") (pin "MM") (pinfunction "33_MM") (pintype "bidirectional"))
    )
    (net (code "160") (name "unconnected-(J4-34-PadNN)") (class "Default")
      (node (ref "J4") (pin "NN") (pinfunction "34_NN") (pintype "bidirectional"))
    )
    (net (code "161") (name "unconnected-(J4-35-PadPP)") (class "Default")
      (node (ref "J4") (pin "PP") (pinfunction "35_PP") (pintype "bidirectional"))
    )
    (net (code "162") (name "unconnected-(J4-36-PadRR)") (class "Default")
      (node (ref "J4") (pin "RR") (pinfunction "36_RR") (pintype "bidirectional"))
    )
    (net (code "163") (name "unconnected-(RN3-Pad8)") (class "Default")
      (node (ref "RN3") (pin "8") (pinfunction "8_8") (pintype "passive"))
    )
    (net (code "164") (name "unconnected-(RN3-Pad9)") (class "Default")
      (node (ref "RN3") (pin "9") (pinfunction "9_9") (pintype "passive"))
    )
    (net (code "165") (name "unconnected-(RN3-Pad10)") (class "Default")
      (node (ref "RN3") (pin "10") (pinfunction "10_10") (pintype "passive"))
    )
    (net (code "166") (name "unconnected-(RN3-Pad11)") (class "Default")
      (node (ref "RN3") (pin "11") (pinfunction "11_11") (pintype "passive"))
    )
    (net (code "167") (name "unconnected-(SV2-Pad6)") (class "Default")
      (node (ref "SV2") (pin "6") (pinfunction "6_6") (pintype "passive"))
    )
    (net (code "168") (name "unconnected-(SV2-Pad7)") (class "Default")
      (node (ref "SV2") (pin "7") (pinfunction "7_7") (pintype "passive"))
    )
    (net (code "169") (name "unconnected-(SV2-Pad8)") (class "Default")
      (node (ref "SV2") (pin "8") (pinfunction "8_8") (pintype "passive"))
    )
    (net (code "170") (name "unconnected-(TS_DISABLE-O-Pad1)") (class "Default")
      (node (ref "TS_DISABLE") (pin "1") (pinfunction "O_1") (pintype "passive"))
    )
    (net (code "171") (name "unconnected-(U2-GPA3-Pad24)") (class "Default")
      (node (ref "U2") (pin "24") (pinfunction "GPA3_24") (pintype "bidirectional"))
    )
    (net (code "172") (name "unconnected-(U2-GPA7-Pad28)") (class "Default")
      (node (ref "U2") (pin "28") (pinfunction "GPA7_28") (pintype "bidirectional"))
    )
    (net (code "173") (name "unconnected-(U2-GPB3-Pad4)") (class "Default")
      (node (ref "U2") (pin "4") (pinfunction "GPB3_4") (pintype "bidirectional"))
    )
    (net (code "174") (name "unconnected-(U2-GPB7-Pad8)") (class "Default")
      (node (ref "U2") (pin "8") (pinfunction "GPB7_8") (pintype "bidirectional"))
    )
    (net (code "175") (name "unconnected-(U2-INTA-Pad20)") (class "Default")
      (node (ref "U2") (pin "20") (pinfunction "INTA_20") (pintype "output"))
    )
    (net (code "176") (name "unconnected-(U2-INTB-Pad19)") (class "Default")
      (node (ref "U2") (pin "19") (pinfunction "INTB_19") (pintype "output"))
    )
    (net (code "177") (name "unconnected-(U7D-O-Pad11)") (class "Default")
      (node (ref "U7") (pin "11") (pinfunction "O_11") (pintype "open_collector"))
    )
    (net (code "178") (name "unconnected-(U10A-T1OUT-Pad14)") (class "Default")
      (node (ref "U10") (pin "14") (pinfunction "T1OUT_14") (pintype "output"))
    )
    (net (code "179") (name "~{BEMA0}") (class "Default")
      (node (ref "E1") (pin "18") (pinfunction "Y1_18") (pintype "tri_state"))
      (node (ref "E2") (pin "4") (pinfunction "A6_4") (pintype "input"))
      (node (ref "E2A") (pin "4") (pinfunction "A6_4") (pintype "input"))
      (node (ref "E5") (pin "4") (pinfunction "A6_4") (pintype "input"))
      (node (ref "E5A") (pin "4") (pinfunction "A6_4") (pintype "input"))
      (node (ref "E9") (pin "9") (pinfunction "C_9") (pintype "input"))
    )
    (net (code "180") (name "~{BEMA1}") (class "Default")
      (node (ref "E1") (pin "16") (pinfunction "Y2_16") (pintype "tri_state"))
      (node (ref "E2") (pin "5") (pinfunction "A5_5") (pintype "input"))
      (node (ref "E2A") (pin "5") (pinfunction "A5_5") (pintype "input"))
      (node (ref "E5") (pin "5") (pinfunction "A5_5") (pintype "input"))
      (node (ref "E5A") (pin "5") (pinfunction "A5_5") (pintype "input"))
      (node (ref "E9") (pin "10") (pinfunction "B_10") (pintype "input"))
    )
    (net (code "181") (name "~{BEMA2}") (class "Default")
      (node (ref "E1") (pin "14") (pinfunction "Y3_14") (pintype "tri_state"))
      (node (ref "E2") (pin "6") (pinfunction "A4_6") (pintype "input"))
      (node (ref "E2A") (pin "6") (pinfunction "A4_6") (pintype "input"))
      (node (ref "E5") (pin "6") (pinfunction "A4_6") (pintype "input"))
      (node (ref "E5A") (pin "6") (pinfunction "A4_6") (pintype "input"))
      (node (ref "E9") (pin "11") (pinfunction "A_11") (pintype "input"))
    )
    (net (code "182") (name "~{BMA00}") (class "Default")
      (node (ref "E1") (pin "9") (pinfunction "Y1_9") (pintype "tri_state"))
      (node (ref "E2") (pin "7") (pinfunction "A3_7") (pintype "input"))
      (node (ref "E2A") (pin "7") (pinfunction "A3_7") (pintype "input"))
      (node (ref "E5") (pin "7") (pinfunction "A3_7") (pintype "input"))
      (node (ref "E5A") (pin "7") (pinfunction "A3_7") (pintype "input"))
    )
    (net (code "183") (name "~{BMA01}") (class "Default")
      (node (ref "E1") (pin "7") (pinfunction "Y2_7") (pintype "tri_state"))
      (node (ref "E2") (pin "8") (pinfunction "A2_8") (pintype "input"))
      (node (ref "E2A") (pin "8") (pinfunction "A2_8") (pintype "input"))
      (node (ref "E5") (pin "8") (pinfunction "A2_8") (pintype "input"))
      (node (ref "E5A") (pin "8") (pinfunction "A2_8") (pintype "input"))
    )
    (net (code "184") (name "~{BMA02}") (class "Default")
      (node (ref "E1") (pin "5") (pinfunction "Y3_5") (pintype "tri_state"))
      (node (ref "E2") (pin "9") (pinfunction "A1_9") (pintype "input"))
      (node (ref "E2A") (pin "9") (pinfunction "A1_9") (pintype "input"))
      (node (ref "E5") (pin "9") (pinfunction "A1_9") (pintype "input"))
      (node (ref "E5A") (pin "9") (pinfunction "A1_9") (pintype "input"))
    )
    (net (code "185") (name "~{BMA03}") (class "Default")
      (node (ref "E1") (pin "3") (pinfunction "Y4_3") (pintype "tri_state"))
      (node (ref "E2") (pin "10") (pinfunction "A0_10") (pintype "input"))
      (node (ref "E2A") (pin "10") (pinfunction "A0_10") (pintype "input"))
      (node (ref "E5") (pin "10") (pinfunction "A0_10") (pintype "input"))
      (node (ref "E5A") (pin "10") (pinfunction "A0_10") (pintype "input"))
    )
    (net (code "186") (name "~{BMA04}") (class "Default")
      (node (ref "E2") (pin "3") (pinfunction "A7_3") (pintype "input"))
      (node (ref "E2A") (pin "3") (pinfunction "A7_3") (pintype "input"))
      (node (ref "E5") (pin "3") (pinfunction "A7_3") (pintype "input"))
      (node (ref "E5A") (pin "3") (pinfunction "A7_3") (pintype "input"))
      (node (ref "E7") (pin "3") (pinfunction "Y4_3") (pintype "tri_state"))
    )
    (net (code "187") (name "~{BMA05}") (class "Default")
      (node (ref "E2") (pin "2") (pinfunction "A12_2") (pintype "input"))
      (node (ref "E2A") (pin "2") (pinfunction "A12_2") (pintype "input"))
      (node (ref "E5") (pin "2") (pinfunction "A12_2") (pintype "input"))
      (node (ref "E5A") (pin "2") (pinfunction "A12_2") (pintype "input"))
      (node (ref "E7") (pin "5") (pinfunction "Y3_5") (pintype "tri_state"))
    )
    (net (code "188") (name "~{BMA06}") (class "Default")
      (node (ref "E2") (pin "1") (pinfunction "A14_1") (pintype "input"))
      (node (ref "E2A") (pin "1") (pinfunction "A14_1") (pintype "input"))
      (node (ref "E5") (pin "1") (pinfunction "A14_1") (pintype "input"))
      (node (ref "E5A") (pin "1") (pinfunction "A14_1") (pintype "input"))
      (node (ref "E7") (pin "7") (pinfunction "Y2_7") (pintype "tri_state"))
    )
    (net (code "189") (name "~{BMA07}") (class "Default")
      (node (ref "E2") (pin "24") (pinfunction "A9_24") (pintype "input"))
      (node (ref "E2A") (pin "24") (pinfunction "A9_24") (pintype "input"))
      (node (ref "E5") (pin "24") (pinfunction "A9_24") (pintype "input"))
      (node (ref "E5A") (pin "24") (pinfunction "A9_24") (pintype "input"))
      (node (ref "E7") (pin "9") (pinfunction "Y1_9") (pintype "tri_state"))
    )
    (net (code "190") (name "~{BMA08}") (class "Default")
      (node (ref "E2") (pin "25") (pinfunction "A8_25") (pintype "input"))
      (node (ref "E2A") (pin "25") (pinfunction "A8_25") (pintype "input"))
      (node (ref "E5") (pin "25") (pinfunction "A8_25") (pintype "input"))
      (node (ref "E5A") (pin "25") (pinfunction "A8_25") (pintype "input"))
      (node (ref "E7") (pin "18") (pinfunction "Y1_18") (pintype "tri_state"))
    )
    (net (code "191") (name "~{BMA09}") (class "Default")
      (node (ref "E2") (pin "26") (pinfunction "A13_26") (pintype "input"))
      (node (ref "E2A") (pin "26") (pinfunction "A13_26") (pintype "input"))
      (node (ref "E5") (pin "26") (pinfunction "A13_26") (pintype "input"))
      (node (ref "E5A") (pin "26") (pinfunction "A13_26") (pintype "input"))
      (node (ref "E7") (pin "16") (pinfunction "Y2_16") (pintype "tri_state"))
    )
    (net (code "192") (name "~{BMA10}") (class "Default")
      (node (ref "E2") (pin "21") (pinfunction "A10_21") (pintype "input"))
      (node (ref "E2A") (pin "21") (pinfunction "A10_21") (pintype "input"))
      (node (ref "E5") (pin "21") (pinfunction "A10_21") (pintype "input"))
      (node (ref "E5A") (pin "21") (pinfunction "A10_21") (pintype "input"))
      (node (ref "E7") (pin "14") (pinfunction "Y3_14") (pintype "tri_state"))
    )
    (net (code "193") (name "~{BMA11}") (class "Default")
      (node (ref "E2") (pin "23") (pinfunction "A11_23") (pintype "input"))
      (node (ref "E2A") (pin "23") (pinfunction "A11_23") (pintype "input"))
      (node (ref "E5") (pin "23") (pinfunction "A11_23") (pintype "input"))
      (node (ref "E5A") (pin "23") (pinfunction "A11_23") (pintype "input"))
      (node (ref "E7") (pin "12") (pinfunction "Y4_12") (pintype "tri_state"))
    )
    (net (code "194") (name "~{BMD_DIR}") (class "Default")
      (node (ref "E6") (pin "14") (pinfunction "Y5_14") (pintype "tri_state"))
      (node (ref "E8") (pin "4") (pinfunction "I1_4") (pintype "input"))
    )
    (net (code "195") (name "~{BREAK_CYCLE}") (class "Default")
      (node (ref "J1") (pin "BL2") (pinfunction "1_BL2") (pintype "bidirectional"))
    )
    (net (code "196") (name "~{BRK_DATA}") (class "Default")
      (node (ref "J1") (pin "BK2") (pinfunction "1_BK2") (pintype "bidirectional"))
      (node (ref "U7") (pin "3") (pinfunction "O_3") (pintype "open_collector"))
    )
    (net (code "197") (name "~{BRK_IN_PROG}") (class "Default")
      (node (ref "J1") (pin "BE2") (pinfunction "1_BE2") (pintype "bidirectional"))
    )
    (net (code "198") (name "~{BSOURCE}") (class "Default")
      (node (ref "E6") (pin "17") (pinfunction "Y2_17") (pintype "tri_state"))
      (node (ref "E6") (pin "4") (pinfunction "A3_4") (pintype "input"))
    )
    (net (code "199") (name "~{BUS_STROBE}") (class "Default")
      (node (ref "J1") (pin "CK1") (pinfunction "1_CK1") (pintype "bidirectional"))
    )
    (net (code "200") (name "~{C0}") (class "Default")
      (node (ref "E14") (pin "35") (pinfunction "IO25_35") (pintype "bidirectional"))
      (node (ref "J1") (pin "CE1") (pinfunction "1_CE1") (pintype "bidirectional"))
    )
    (net (code "201") (name "~{C1}") (class "Default")
      (node (ref "E14") (pin "33") (pinfunction "IO23_33") (pintype "bidirectional"))
      (node (ref "J1") (pin "CH1") (pinfunction "1_CH1") (pintype "bidirectional"))
    )
    (net (code "202") (name "~{C2}") (class "Default")
      (node (ref "J1") (pin "CJ1") (pinfunction "1_CJ1") (pintype "bidirectional"))
    )
    (net (code "203") (name "~{CE_OK}") (class "Default")
      (node (ref "C22") (pin "2") (pinfunction "2_2") (pintype "passive"))
      (node (ref "E8") (pin "12") (pinfunction "O_12") (pintype "output"))
      (node (ref "Q3") (pin "3") (pinfunction "E_3") (pintype "passive"))
    )
    (net (code "204") (name "~{CE}") (class "Default")
      (node (ref "C22") (pin "1") (pinfunction "1_1") (pintype "passive"))
      (node (ref "E2") (pin "20") (pinfunction "~{CE}_20") (pintype "input"))
      (node (ref "E2A") (pin "20") (pinfunction "~{CS}_20") (pintype "input"))
      (node (ref "E5") (pin "20") (pinfunction "~{CE}_20") (pintype "input"))
      (node (ref "E5A") (pin "20") (pinfunction "~{CS}_20") (pintype "input"))
      (node (ref "Q3") (pin "1") (pinfunction "C_1") (pintype "passive"))
      (node (ref "R15") (pin "1") (pinfunction "1_1") (pintype "passive"))
    )
    (net (code "205") (name "~{CPMA_DISABLE}") (class "Default")
      (node (ref "E14") (pin "21") (pinfunction "IO14_21") (pintype "bidirectional"))
      (node (ref "J1") (pin "CU1") (pinfunction "1_CU1") (pintype "bidirectional"))
    )
    (net (code "206") (name "~{DATA00}") (class "Default")
      (node (ref "E14") (pin "61") (pinfunction "IO45_61") (pintype "bidirectional"))
      (node (ref "J1") (pin "AR1") (pinfunction "1_AR1") (pintype "bidirectional"))
      (node (ref "U3") (pin "3") (pinfunction "O_3") (pintype "open_collector"))
    )
    (net (code "207") (name "~{DATA01}") (class "Default")
      (node (ref "E14") (pin "60") (pinfunction "IO44_60") (pintype "bidirectional"))
      (node (ref "J1") (pin "AS1") (pinfunction "1_AS1") (pintype "bidirectional"))
      (node (ref "U3") (pin "6") (pinfunction "O_6") (pintype "open_collector"))
    )
    (net (code "208") (name "~{DATA02}") (class "Default")
      (node (ref "E14") (pin "58") (pinfunction "IO43_58") (pintype "bidirectional"))
      (node (ref "J1") (pin "AU1") (pinfunction "1_AU1") (pintype "bidirectional"))
      (node (ref "U3") (pin "11") (pinfunction "O_11") (pintype "open_collector"))
    )
    (net (code "209") (name "~{DATA03}") (class "Default")
      (node (ref "E14") (pin "57") (pinfunction "IO42_57") (pintype "bidirectional"))
      (node (ref "J1") (pin "AV1") (pinfunction "1_AV1") (pintype "bidirectional"))
      (node (ref "U3") (pin "8") (pinfunction "O_8") (pintype "open_collector"))
    )
    (net (code "210") (name "~{DATA04}") (class "Default")
      (node (ref "E14") (pin "46") (pinfunction "IO33_46") (pintype "bidirectional"))
      (node (ref "J1") (pin "BR1") (pinfunction "1_BR1") (pintype "bidirectional"))
      (node (ref "U4") (pin "3") (pinfunction "O_3") (pintype "open_collector"))
    )
    (net (code "211") (name "~{DATA05}") (class "Default")
      (node (ref "E14") (pin "45") (pinfunction "IO/PD2_45") (pintype "bidirectional"))
      (node (ref "J1") (pin "BS1") (pinfunction "1_BS1") (pintype "bidirectional"))
      (node (ref "U4") (pin "6") (pinfunction "O_6") (pintype "open_collector"))
    )
    (net (code "212") (name "~{DATA06}") (class "Default")
      (node (ref "E14") (pin "44") (pinfunction "IO31_44") (pintype "bidirectional"))
      (node (ref "J1") (pin "BU1") (pinfunction "1_BU1") (pintype "bidirectional"))
      (node (ref "U4") (pin "11") (pinfunction "O_11") (pintype "open_collector"))
    )
    (net (code "213") (name "~{DATA07}") (class "Default")
      (node (ref "E14") (pin "40") (pinfunction "IO29_40") (pintype "bidirectional"))
      (node (ref "J1") (pin "BV1") (pinfunction "1_BV1") (pintype "bidirectional"))
      (node (ref "U4") (pin "8") (pinfunction "O_8") (pintype "open_collector"))
    )
    (net (code "214") (name "~{DATA08}") (class "Default")
      (node (ref "E14") (pin "4") (pinfunction "IO1_4") (pintype "bidirectional"))
      (node (ref "J1") (pin "DR1") (pinfunction "1_DR1") (pintype "bidirectional"))
      (node (ref "U5") (pin "3") (pinfunction "O_3") (pintype "open_collector"))
    )
    (net (code "215") (name "~{DATA09}") (class "Default")
      (node (ref "E14") (pin "81") (pinfunction "IO/GCLK3_81") (pintype "bidirectional"))
      (node (ref "J1") (pin "DS1") (pinfunction "1_DS1") (pintype "bidirectional"))
      (node (ref "U5") (pin "6") (pinfunction "O_6") (pintype "open_collector"))
    )
    (net (code "216") (name "~{DATA10}") (class "Default")
      (node (ref "E14") (pin "80") (pinfunction "IO59_80") (pintype "bidirectional"))
      (node (ref "J1") (pin "DU1") (pinfunction "1_DU1") (pintype "bidirectional"))
      (node (ref "U5") (pin "11") (pinfunction "O_11") (pintype "open_collector"))
    )
    (net (code "217") (name "~{DATA11}") (class "Default")
      (node (ref "E14") (pin "77") (pinfunction "IO57_77") (pintype "bidirectional"))
      (node (ref "J1") (pin "DV1") (pinfunction "1_DV1") (pintype "bidirectional"))
      (node (ref "U5") (pin "8") (pinfunction "O_8") (pintype "open_collector"))
    )
    (net (code "218") (name "~{DISABLE}") (class "Default")
      (node (ref "E8") (pin "1") (pinfunction "I0_1") (pintype "input"))
      (node (ref "E8") (pin "10") (pinfunction "I1_10") (pintype "input"))
      (node (ref "E8") (pin "11") (pinfunction "I2_11") (pintype "input"))
      (node (ref "E8") (pin "2") (pinfunction "I1_2") (pintype "input"))
      (node (ref "E9") (pin "5") (pinfunction "Y_5") (pintype "output"))
    )
    (net (code "219") (name "~{D}") (class "Default")
      (node (ref "E14") (pin "11") (pinfunction "IO7_11") (pintype "bidirectional"))
      (node (ref "J1") (pin "DK2") (pinfunction "1_DK2") (pintype "bidirectional"))
    )
    (net (code "220") (name "~{EMA0}") (class "Default")
      (node (ref "E1") (pin "2") (pinfunction "A1_2") (pintype "input"))
      (node (ref "E14") (pin "70") (pinfunction "IO52_70") (pintype "bidirectional"))
      (node (ref "J1") (pin "AD2") (pinfunction "1_AD2") (pintype "bidirectional"))
    )
    (net (code "221") (name "~{EMA1}") (class "Default")
      (node (ref "E1") (pin "4") (pinfunction "A2_4") (pintype "input"))
      (node (ref "E14") (pin "69") (pinfunction "IO51_69") (pintype "bidirectional"))
      (node (ref "J1") (pin "AE2") (pinfunction "1_AE2") (pintype "bidirectional"))
    )
    (net (code "222") (name "~{EMA2}") (class "Default")
      (node (ref "E1") (pin "6") (pinfunction "A3_6") (pintype "input"))
      (node (ref "E14") (pin "68") (pinfunction "IO50_68") (pintype "bidirectional"))
      (node (ref "J1") (pin "AH2") (pinfunction "1_AH2") (pintype "bidirectional"))
    )
    (net (code "223") (name "~{E}") (class "Default")
      (node (ref "J1") (pin "DL2") (pinfunction "1_DL2") (pintype "bidirectional"))
    )
    (net (code "224") (name "~{F_SET}") (class "Default")
      (node (ref "E14") (pin "5") (pinfunction "IO2_5") (pintype "bidirectional"))
      (node (ref "J1") (pin "DP2") (pinfunction "1_DP2") (pintype "bidirectional"))
    )
    (net (code "225") (name "~{F}") (class "Default")
      (node (ref "E14") (pin "15") (pinfunction "IO9_15") (pintype "bidirectional"))
      (node (ref "J1") (pin "DJ2") (pinfunction "1_DJ2") (pintype "bidirectional"))
    )
    (net (code "226") (name "~{IND1}") (class "Default")
      (node (ref "E14") (pin "20") (pinfunction "IO13_20") (pintype "bidirectional"))
      (node (ref "J1") (pin "CU2") (pinfunction "1_CU2") (pintype "bidirectional"))
    )
    (net (code "227") (name "~{IND2}") (class "Default")
      (node (ref "E14") (pin "18") (pinfunction "IO12_18") (pintype "bidirectional"))
      (node (ref "J1") (pin "CV2") (pinfunction "1_CV2") (pintype "bidirectional"))
    )
    (net (code "228") (name "~{INTERNAL_IO}") (class "Default")
      (node (ref "E14") (pin "28") (pinfunction "IO19_28") (pintype "bidirectional"))
      (node (ref "J1") (pin "CL1") (pinfunction "1_CL1") (pintype "bidirectional"))
    )
    (net (code "229") (name "~{INT_IN_PROG}") (class "Default")
      (node (ref "E14") (pin "48") (pinfunction "IO34_48") (pintype "bidirectional"))
      (node (ref "J1") (pin "BP2") (pinfunction "1_BP2") (pintype "bidirectional"))
    )
    (net (code "230") (name "~{INT_RQST}") (class "Default")
      (node (ref "E14") (pin "25") (pinfunction "IO17_25") (pintype "bidirectional"))
      (node (ref "J1") (pin "CP1") (pinfunction "1_CP1") (pintype "bidirectional"))
    )
    (net (code "231") (name "~{IO_PAUSE}") (class "Default")
      (node (ref "E14") (pin "36") (pinfunction "IO26_36") (pintype "bidirectional"))
      (node (ref "J1") (pin "CD1") (pinfunction "1_CD1") (pintype "bidirectional"))
    )
    (net (code "232") (name "~{IR00}") (class "Default")
      (node (ref "E14") (pin "17") (pinfunction "IO11_17") (pintype "bidirectional"))
      (node (ref "J1") (pin "DD2") (pinfunction "1_DD2") (pintype "bidirectional"))
    )
    (net (code "233") (name "~{IR01}") (class "Default")
      (node (ref "E14") (pin "16") (pinfunction "IO10_16") (pintype "bidirectional"))
      (node (ref "J1") (pin "DE2") (pinfunction "1_DE2") (pintype "bidirectional"))
    )
    (net (code "234") (name "~{IR2}") (class "Default")
      (node (ref "J1") (pin "DH2") (pinfunction "1_DH2") (pintype "bidirectional"))
    )
    (net (code "235") (name "~{KEY_CTL}") (class "Default")
      (node (ref "E14") (pin "79") (pinfunction "IO58_79") (pintype "bidirectional"))
      (node (ref "J1") (pin "DU2") (pinfunction "1_DU2") (pintype "bidirectional"))
      (node (ref "U6") (pin "11") (pinfunction "O_11") (pintype "open_collector"))
    )
    (net (code "236") (name "~{LA_ENABLE}") (class "Default")
      (node (ref "J1") (pin "BM2") (pinfunction "1_BM2") (pintype "bidirectional"))
      (node (ref "U6") (pin "6") (pinfunction "O_6") (pintype "open_collector"))
    )
    (net (code "237") (name "~{LINK_DATA}") (class "Default")
      (node (ref "J1") (pin "CR2") (pinfunction "1_CR2") (pintype "bidirectional"))
    )
    (net (code "238") (name "~{LINK_LOAD}") (class "Default")
      (node (ref "J1") (pin "CS2") (pinfunction "1_CS2") (pintype "bidirectional"))
    )
    (net (code "239") (name "~{LINK}") (class "Default")
      (node (ref "J1") (pin "AV2") (pinfunction "1_AV2") (pintype "bidirectional"))
    )
    (net (code "240") (name "~{LOAD_CONT}") (class "Default")
      (node (ref "E14") (pin "54") (pinfunction "IO39_54") (pintype "bidirectional"))
      (node (ref "J1") (pin "BH2") (pinfunction "1_BH2") (pintype "bidirectional"))
    )
    (net (code "241") (name "~{MA00}") (class "Default")
      (node (ref "E1") (pin "11") (pinfunction "A1_11") (pintype "input"))
      (node (ref "J1") (pin "AD1") (pinfunction "1_AD1") (pintype "bidirectional"))
    )
    (net (code "242") (name "~{MA01}") (class "Default")
      (node (ref "E1") (pin "13") (pinfunction "A2_13") (pintype "input"))
      (node (ref "J1") (pin "AE1") (pinfunction "1_AE1") (pintype "bidirectional"))
    )
    (net (code "243") (name "~{MA02}") (class "Default")
      (node (ref "E1") (pin "15") (pinfunction "A3_15") (pintype "input"))
      (node (ref "J1") (pin "AH1") (pinfunction "1_AH1") (pintype "bidirectional"))
    )
    (net (code "244") (name "~{MA03}") (class "Default")
      (node (ref "E1") (pin "17") (pinfunction "A4_17") (pintype "input"))
      (node (ref "J1") (pin "AJ1") (pinfunction "1_AJ1") (pintype "bidirectional"))
    )
    (net (code "245") (name "~{MA04}") (class "Default")
      (node (ref "E7") (pin "17") (pinfunction "A4_17") (pintype "input"))
      (node (ref "J1") (pin "BD1") (pinfunction "1_BD1") (pintype "bidirectional"))
    )
    (net (code "246") (name "~{MA05}") (class "Default")
      (node (ref "E7") (pin "15") (pinfunction "A3_15") (pintype "input"))
      (node (ref "J1") (pin "BE1") (pinfunction "1_BE1") (pintype "bidirectional"))
    )
    (net (code "247") (name "~{MA06}") (class "Default")
      (node (ref "E7") (pin "13") (pinfunction "A2_13") (pintype "input"))
      (node (ref "J1") (pin "BH1") (pinfunction "1_BH1") (pintype "bidirectional"))
    )
    (net (code "248") (name "~{MA07}") (class "Default")
      (node (ref "E7") (pin "11") (pinfunction "A1_11") (pintype "input"))
      (node (ref "J1") (pin "BJ1") (pinfunction "1_BJ1") (pintype "bidirectional"))
    )
    (net (code "249") (name "~{MA08}") (class "Default")
      (node (ref "E7") (pin "2") (pinfunction "A1_2") (pintype "input"))
      (node (ref "J1") (pin "DD1") (pinfunction "1_DD1") (pintype "bidirectional"))
    )
    (net (code "250") (name "~{MA09}") (class "Default")
      (node (ref "E7") (pin "4") (pinfunction "A2_4") (pintype "input"))
      (node (ref "J1") (pin "DE1") (pinfunction "1_DE1") (pintype "bidirectional"))
    )
    (net (code "251") (name "~{MA10}") (class "Default")
      (node (ref "E7") (pin "6") (pinfunction "A3_6") (pintype "input"))
      (node (ref "J1") (pin "DH1") (pinfunction "1_DH1") (pintype "bidirectional"))
    )
    (net (code "252") (name "~{MA11}") (class "Default")
      (node (ref "E7") (pin "8") (pinfunction "A4_8") (pintype "input"))
      (node (ref "J1") (pin "DJ1") (pinfunction "1_DJ1") (pintype "bidirectional"))
    )
    (net (code "253") (name "~{MD00}") (class "Default")
      (node (ref "E14") (pin "67") (pinfunction "IO49_67") (pintype "bidirectional"))
      (node (ref "E3") (pin "1") (pinfunction "I0_1") (pintype "input"))
      (node (ref "E3") (pin "6") (pinfunction "O_6") (pintype "open_collector"))
      (node (ref "J1") (pin "AK1") (pinfunction "1_AK1") (pintype "bidirectional"))
    )
    (net (code "254") (name "~{MD01}") (class "Default")
      (node (ref "E14") (pin "65") (pinfunction "IO48_65") (pintype "bidirectional"))
      (node (ref "E3") (pin "12") (pinfunction "I0_12") (pintype "input"))
      (node (ref "E3") (pin "8") (pinfunction "O_8") (pintype "open_collector"))
      (node (ref "J1") (pin "AL1") (pinfunction "1_AL1") (pintype "bidirectional"))
    )
    (net (code "255") (name "~{MD02}") (class "Default")
      (node (ref "E14") (pin "64") (pinfunction "IO47_64") (pintype "bidirectional"))
      (node (ref "E4") (pin "1") (pinfunction "I0_1") (pintype "input"))
      (node (ref "E4") (pin "6") (pinfunction "O_6") (pintype "open_collector"))
      (node (ref "J1") (pin "AM1") (pinfunction "1_AM1") (pintype "bidirectional"))
    )
    (net (code "256") (name "~{MD03}") (class "Default")
      (node (ref "E14") (pin "63") (pinfunction "IO46_63") (pintype "bidirectional"))
      (node (ref "E4") (pin "12") (pinfunction "I0_12") (pintype "input"))
      (node (ref "E4") (pin "8") (pinfunction "O_8") (pintype "open_collector"))
      (node (ref "J1") (pin "AP1") (pinfunction "1_AP1") (pintype "bidirectional"))
    )
    (net (code "257") (name "~{MD04}") (class "Default")
      (node (ref "E10") (pin "1") (pinfunction "I0_1") (pintype "input"))
      (node (ref "E10") (pin "6") (pinfunction "O_6") (pintype "open_collector"))
      (node (ref "E14") (pin "52") (pinfunction "IO38_52") (pintype "bidirectional"))
      (node (ref "J1") (pin "BK1") (pinfunction "1_BK1") (pintype "bidirectional"))
    )
    (net (code "258") (name "~{MD05}") (class "Default")
      (node (ref "E10") (pin "12") (pinfunction "I0_12") (pintype "input"))
      (node (ref "E10") (pin "8") (pinfunction "O_8") (pintype "open_collector"))
      (node (ref "E14") (pin "51") (pinfunction "IO37_51") (pintype "bidirectional"))
      (node (ref "J1") (pin "BL1") (pinfunction "1_BL1") (pintype "bidirectional"))
    )
    (net (code "259") (name "~{MD06}") (class "Default")
      (node (ref "E11") (pin "1") (pinfunction "I0_1") (pintype "input"))
      (node (ref "E11") (pin "6") (pinfunction "O_6") (pintype "open_collector"))
      (node (ref "E14") (pin "50") (pinfunction "IO36_50") (pintype "bidirectional"))
      (node (ref "J1") (pin "BM1") (pinfunction "1_BM1") (pintype "bidirectional"))
    )
    (net (code "260") (name "~{MD07}") (class "Default")
      (node (ref "E11") (pin "12") (pinfunction "I0_12") (pintype "input"))
      (node (ref "E11") (pin "8") (pinfunction "O_8") (pintype "open_collector"))
      (node (ref "E14") (pin "49") (pinfunction "IO35_49") (pintype "bidirectional"))
      (node (ref "J1") (pin "BP1") (pinfunction "1_BP1") (pintype "bidirectional"))
    )
    (net (code "261") (name "~{MD08}") (class "Default")
      (node (ref "E12") (pin "1") (pinfunction "I0_1") (pintype "input"))
      (node (ref "E12") (pin "6") (pinfunction "O_6") (pintype "open_collector"))
      (node (ref "E14") (pin "12") (pinfunction "IO/PD1_12") (pintype "bidirectional"))
      (node (ref "J1") (pin "DK1") (pinfunction "1_DK1") (pintype "bidirectional"))
    )
    (net (code "262") (name "~{MD09}") (class "Default")
      (node (ref "E12") (pin "12") (pinfunction "I0_12") (pintype "input"))
      (node (ref "E12") (pin "8") (pinfunction "O_8") (pintype "open_collector"))
      (node (ref "E14") (pin "10") (pinfunction "IO6_10") (pintype "bidirectional"))
      (node (ref "J1") (pin "DL1") (pinfunction "1_DL1") (pintype "bidirectional"))
    )
    (net (code "263") (name "~{MD10}") (class "Default")
      (node (ref "E13") (pin "1") (pinfunction "I0_1") (pintype "input"))
      (node (ref "E13") (pin "6") (pinfunction "O_6") (pintype "open_collector"))
      (node (ref "E14") (pin "9") (pinfunction "IO5_9") (pintype "bidirectional"))
      (node (ref "J1") (pin "DM1") (pinfunction "1_DM1") (pintype "bidirectional"))
    )
    (net (code "264") (name "~{MD11}") (class "Default")
      (node (ref "E13") (pin "12") (pinfunction "I0_12") (pintype "input"))
      (node (ref "E13") (pin "8") (pinfunction "O_8") (pintype "open_collector"))
      (node (ref "E14") (pin "6") (pinfunction "IO3_6") (pintype "bidirectional"))
      (node (ref "J1") (pin "DP1") (pinfunction "1_DP1") (pintype "bidirectional"))
    )
    (net (code "265") (name "~{MD_DIR}") (class "Default")
      (node (ref "E6") (pin "5") (pinfunction "A4_5") (pintype "input"))
      (node (ref "J1") (pin "AK2") (pinfunction "1_AK2") (pintype "bidirectional"))
      (node (ref "U7") (pin "6") (pinfunction "O_6") (pintype "open_collector"))
    )
    (net (code "266") (name "~{MEM_START}") (class "Default")
      (node (ref "J1") (pin "AJ2") (pinfunction "1_AJ2") (pintype "bidirectional"))
      (node (ref "U6") (pin "3") (pinfunction "O_3") (pintype "open_collector"))
    )
    (net (code "267") (name "~{MS_DISABLE}") (class "Default")
      (node (ref "J1") (pin "CV1") (pinfunction "1_CV1") (pintype "bidirectional"))
      (node (ref "U6") (pin "8") (pinfunction "O_8") (pintype "open_collector"))
    )
    (net (code "268") (name "~{NOT_LAST_TR}") (class "Default")
      (node (ref "J1") (pin "CM1") (pinfunction "1_CM1") (pintype "bidirectional"))
    )
    (net (code "269") (name "~{NTS_STALL}") (class "Default")
      (node (ref "J1") (pin "BR2") (pinfunction "1_BR2") (pintype "bidirectional"))
    )
    (net (code "270") (name "~{OE}") (class "Default")
      (node (ref "E2") (pin "22") (pinfunction "~{OE}_22") (pintype "input"))
      (node (ref "E2A") (pin "22") (pinfunction "~{OE}_22") (pintype "input"))
      (node (ref "E5") (pin "22") (pinfunction "~{OE}_22") (pintype "input"))
      (node (ref "E5A") (pin "22") (pinfunction "~{OE}_22") (pintype "input"))
      (node (ref "E6") (pin "8") (pinfunction "A7_8") (pintype "input"))
      (node (ref "E8") (pin "8") (pinfunction "O_8") (pintype "output"))
    )
    (net (code "271") (name "~{OVERFLOW}") (class "Default")
      (node (ref "J1") (pin "BJ2") (pinfunction "1_BJ2") (pintype "bidirectional"))
    )
    (net (code "272") (name "~{RESET}") (class "Default")
      (node (ref "C11") (pin "1") (pinfunction "1_1") (pintype "passive"))
      (node (ref "D1") (pin "A") (pinfunction "A_A") (pintype "passive"))
      (node (ref "J3") (pin "5") (pinfunction "5_5") (pintype "passive"))
      (node (ref "R19") (pin "1") (pinfunction "1_1") (pintype "passive"))
      (node (ref "U1") (pin "1") (pinfunction "PC6(/RESET)_1") (pintype "bidirectional"))
    )
    (net (code "273") (name "~{ROM_ADDR}") (class "Default")
      (node (ref "E6") (pin "9") (pinfunction "A8_9") (pintype "input"))
      (node (ref "J1") (pin "AU2") (pinfunction "1_AU2") (pintype "bidirectional"))
    )
    (net (code "274") (name "~{RUN}") (class "Default")
      (node (ref "E14") (pin "41") (pinfunction "IO30_41") (pintype "bidirectional"))
      (node (ref "J1") (pin "BU2") (pinfunction "1_BU2") (pintype "bidirectional"))
      (node (ref "R2") (pin "2") (pinfunction "2_2") (pintype "passive"))
    )
    (net (code "275") (name "~{SKIP}") (class "Default")
      (node (ref "E14") (pin "22") (pinfunction "IO15_22") (pintype "bidirectional"))
      (node (ref "J1") (pin "CS1") (pinfunction "1_CS1") (pintype "bidirectional"))
    )
    (net (code "276") (name "~{STOP}") (class "Default")
      (node (ref "J1") (pin "DS2") (pinfunction "1_DS2") (pintype "bidirectional"))
      (node (ref "U7") (pin "8") (pinfunction "O_8") (pintype "open_collector"))
    )
    (net (code "277") (name "~{TP4}") (class "Default")
      (node (ref "E6") (pin "18") (pinfunction "Y1_18") (pintype "tri_state"))
      (node (ref "E8") (pin "13") (pinfunction "I2_13") (pintype "input"))
    )
    (net (code "278") (name "~{TS1}") (class "Default")
      (node (ref "E14") (pin "29") (pinfunction "IO20_29") (pintype "bidirectional"))
      (node (ref "J1") (pin "CK2") (pinfunction "1_CK2") (pintype "bidirectional"))
    )
    (net (code "279") (name "~{TS2}") (class "Default")
      (node (ref "J1") (pin "CL2") (pinfunction "1_CL2") (pintype "bidirectional"))
    )
    (net (code "280") (name "~{TS3}") (class "Default")
      (node (ref "E14") (pin "27") (pinfunction "IO18_27") (pintype "bidirectional"))
      (node (ref "J1") (pin "CM2") (pinfunction "1_CM2") (pintype "bidirectional"))
    )
    (net (code "281") (name "~{TS4}") (class "Default")
      (node (ref "J1") (pin "CP2") (pinfunction "1_CP2") (pintype "bidirectional"))
      (node (ref "U8") (pin "13") (pinfunction "I2_13") (pintype "input"))
    )
    (net (code "282") (name "~{USER_MODE}") (class "Default")
      (node (ref "E14") (pin "8") (pinfunction "IO4_8") (pintype "bidirectional"))
      (node (ref "J1") (pin "DM2") (pinfunction "1_DM2") (pintype "bidirectional"))
    )
    (net (code "283") (name "~{WE}") (class "Default")
      (node (ref "E2") (pin "27") (pinfunction "~{WE}_27") (pintype "input"))
      (node (ref "E2A") (pin "27") (pinfunction "~{WE}_27") (pintype "input"))
      (node (ref "E5") (pin "27") (pinfunction "~{WE}_27") (pintype "input"))
      (node (ref "E5A") (pin "27") (pinfunction "~{WE}_27") (pintype "input"))
      (node (ref "E6") (pin "7") (pinfunction "A6_7") (pintype "input"))
      (node (ref "E8") (pin "6") (pinfunction "O_6") (pintype "output"))
    )
    (net (code "284") (name "~{W_KEY_CONTROL}") (class "Default")
      (node (ref "U1") (pin "13") (pinfunction "PD7(AIN1)_13") (pintype "bidirectional"))
      (node (ref "U6") (pin "12") (pinfunction "I0_12") (pintype "input"))
    )
    (net (code "285") (name "~{W_LA_ENABLE}") (class "Default")
      (node (ref "U1") (pin "11") (pinfunction "PD5(T1)_11") (pintype "bidirectional"))
      (node (ref "U6") (pin "4") (pinfunction "I0_4") (pintype "input"))
    )
    (net (code "286") (name "~{W_MEM_START}") (class "Default")
      (node (ref "R7") (pin "2") (pinfunction "2_2") (pintype "passive"))
      (node (ref "U1") (pin "25") (pinfunction "PC2(ADC2)_25") (pintype "bidirectional"))
      (node (ref "U6") (pin "1") (pinfunction "I0_1") (pintype "input"))
      (node (ref "U6") (pin "2") (pinfunction "I1_2") (pintype "input"))
    )
    (net (code "287") (name "~{W_MS_IR_DISABLE}") (class "Default")
      (node (ref "U1") (pin "12") (pinfunction "PD6(AIN0)_12") (pintype "bidirectional"))
      (node (ref "U6") (pin "9") (pinfunction "I0_9") (pintype "input"))
    )
  )
)
